# Reach_B0.net
KiCad netlist of a schematic drawn in EAGLE
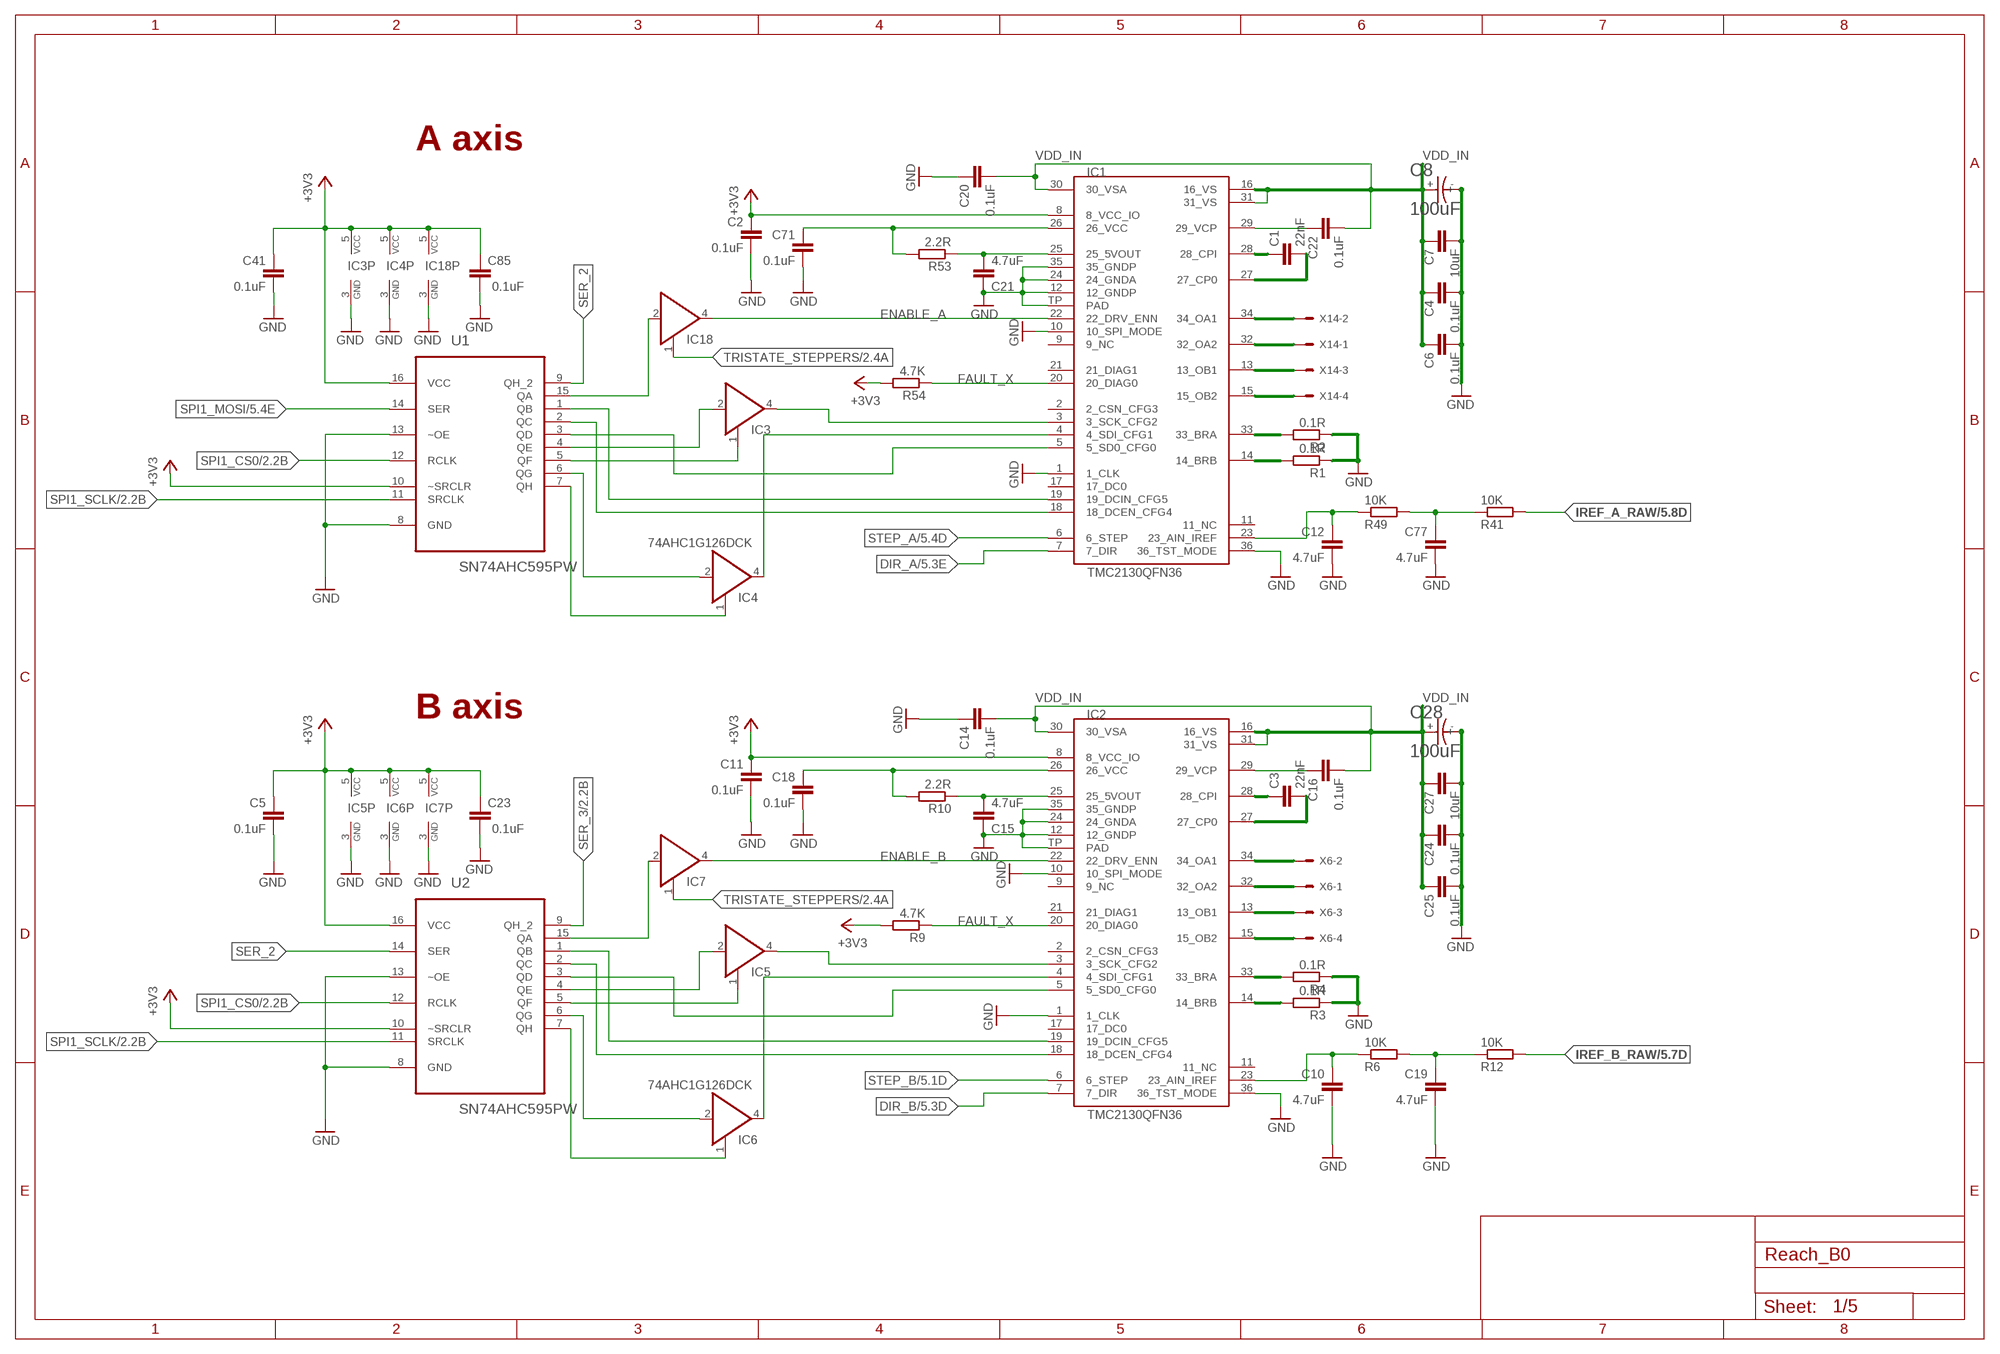
[diagram p0: schematic, sheet 1]
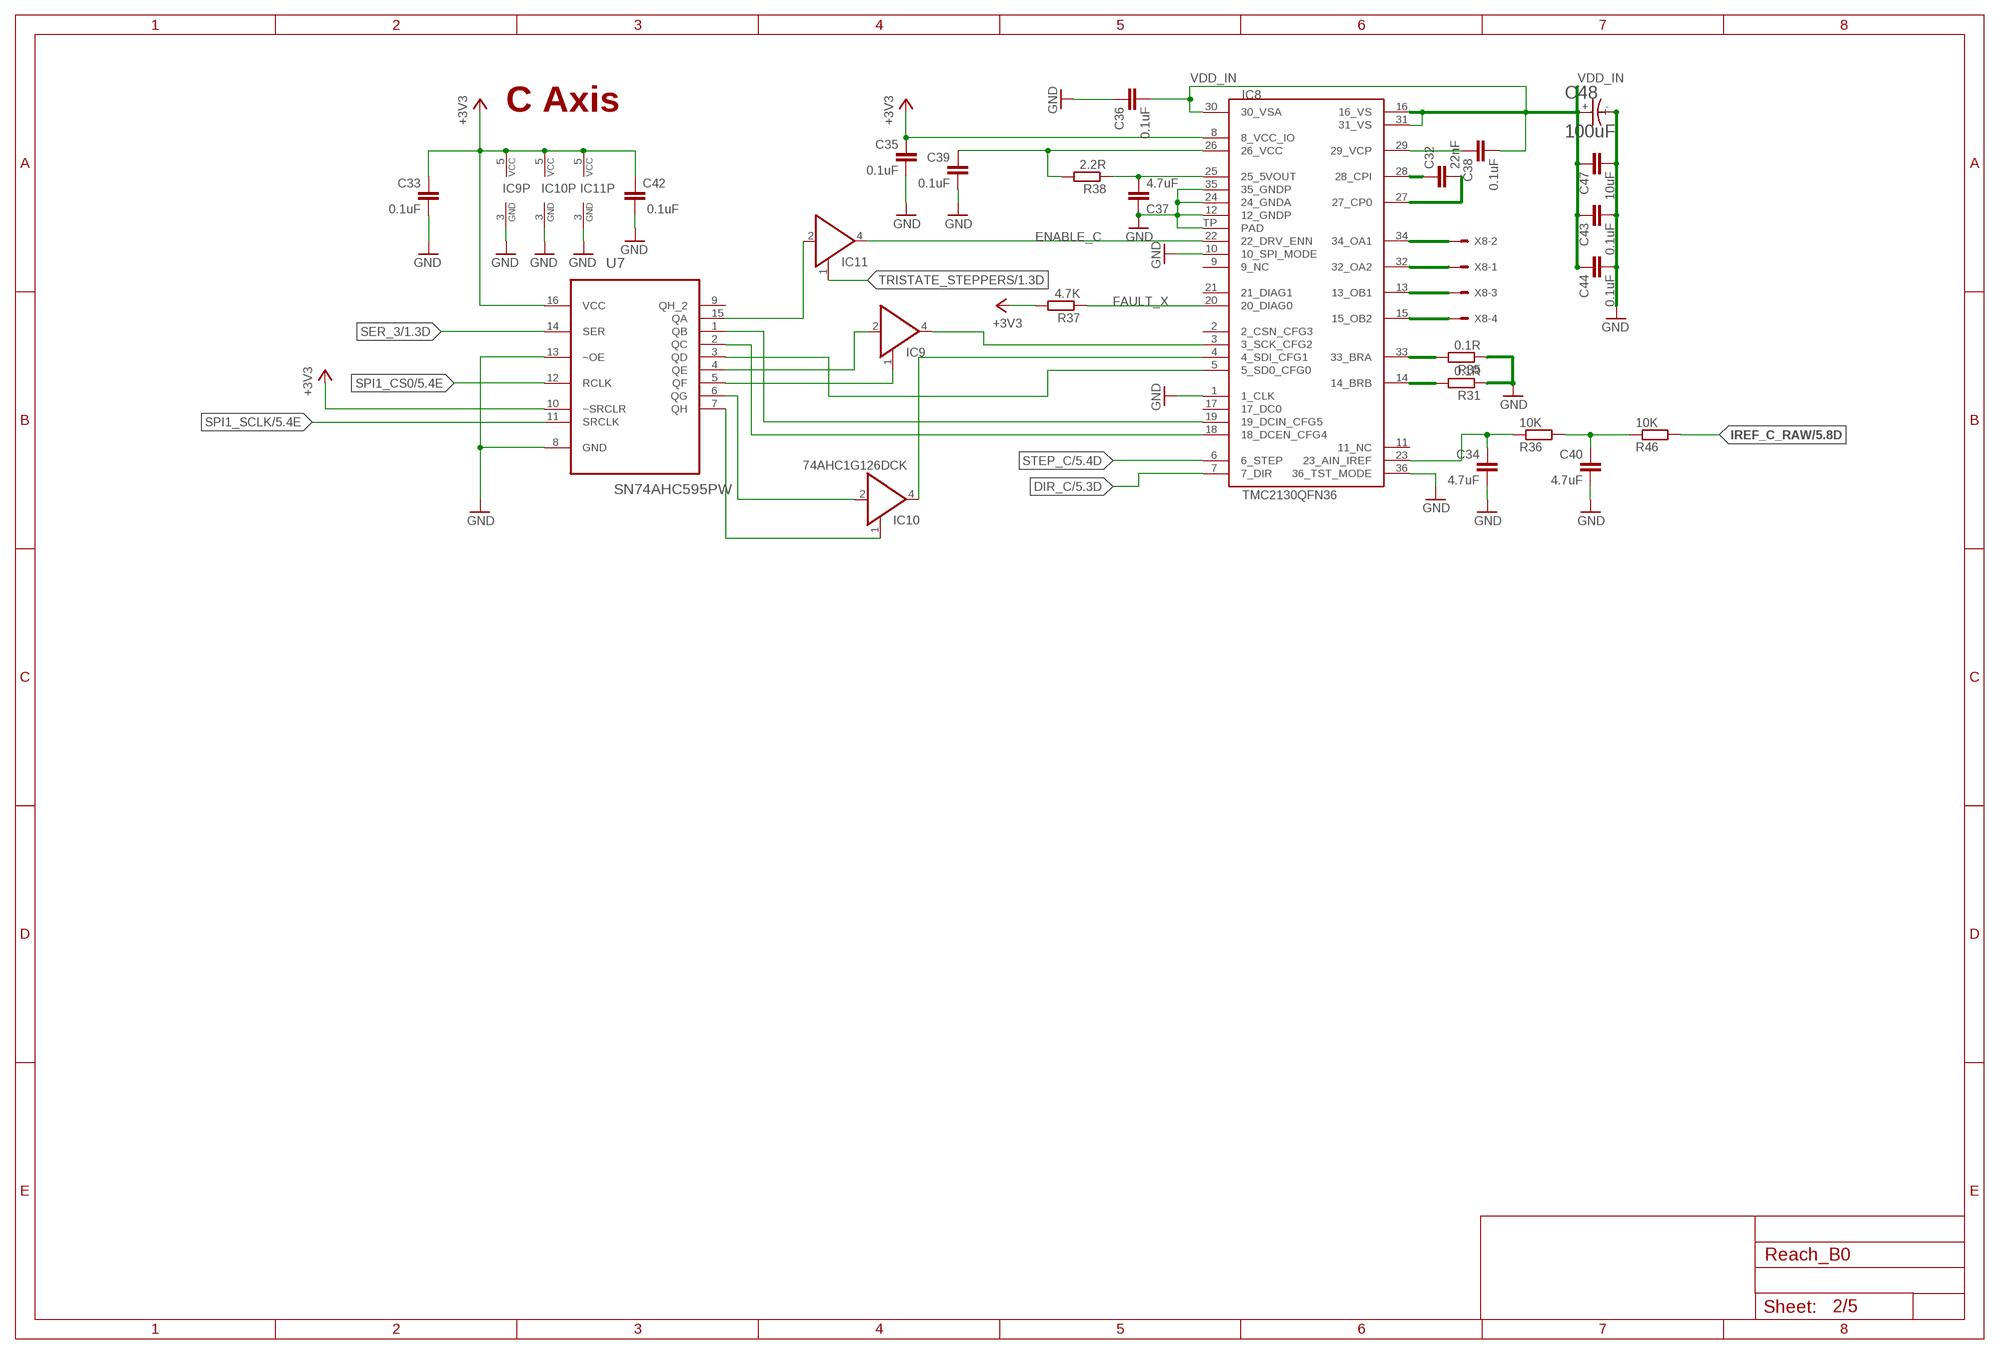
[diagram p1: schematic, sheet 2]
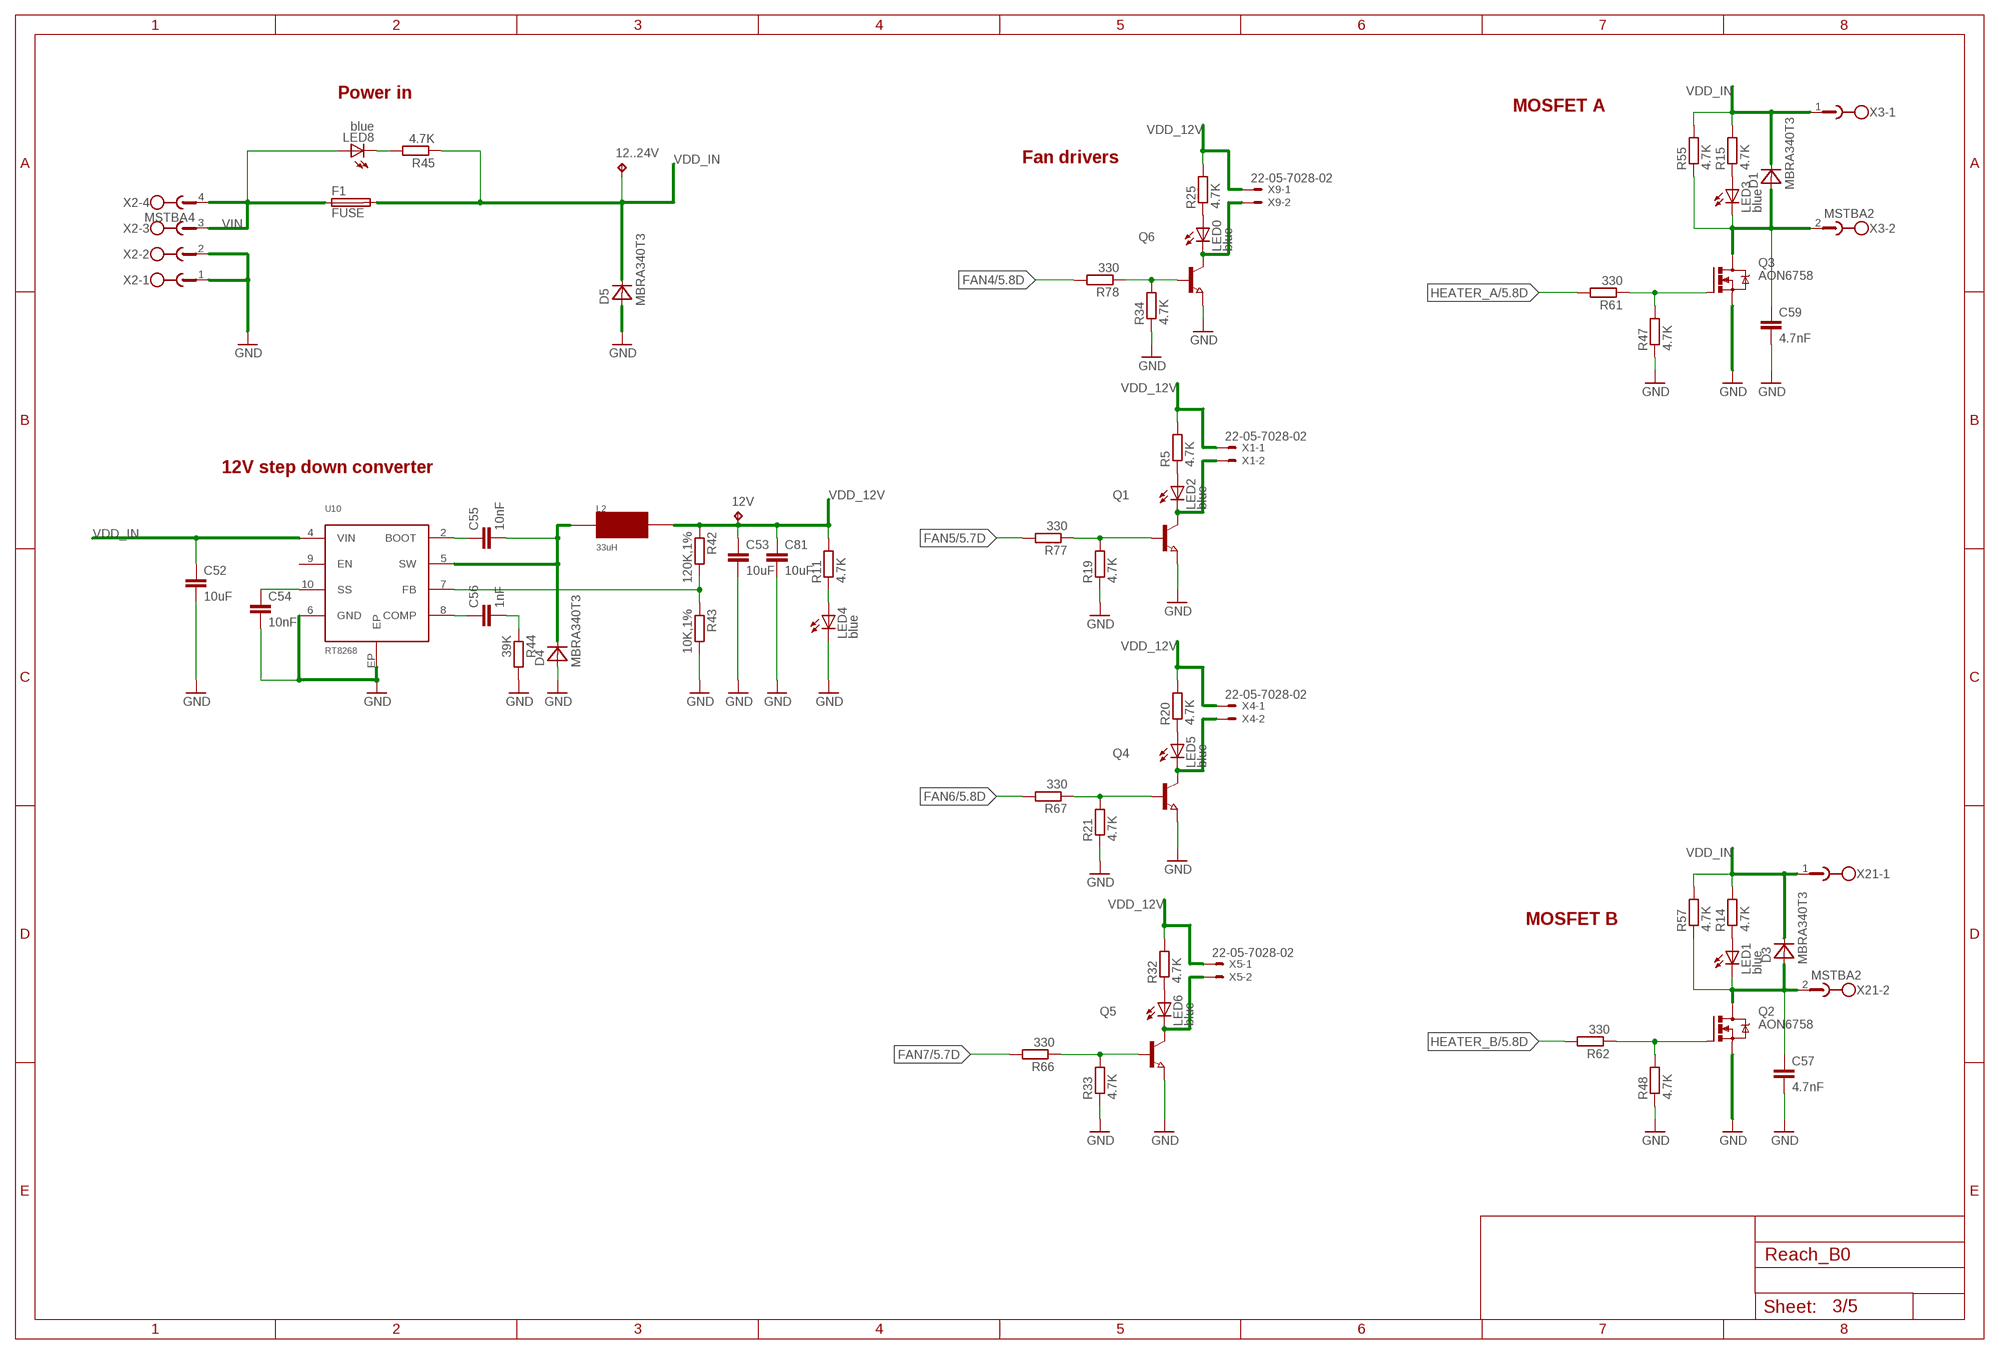
[diagram p2: schematic, sheet 3]
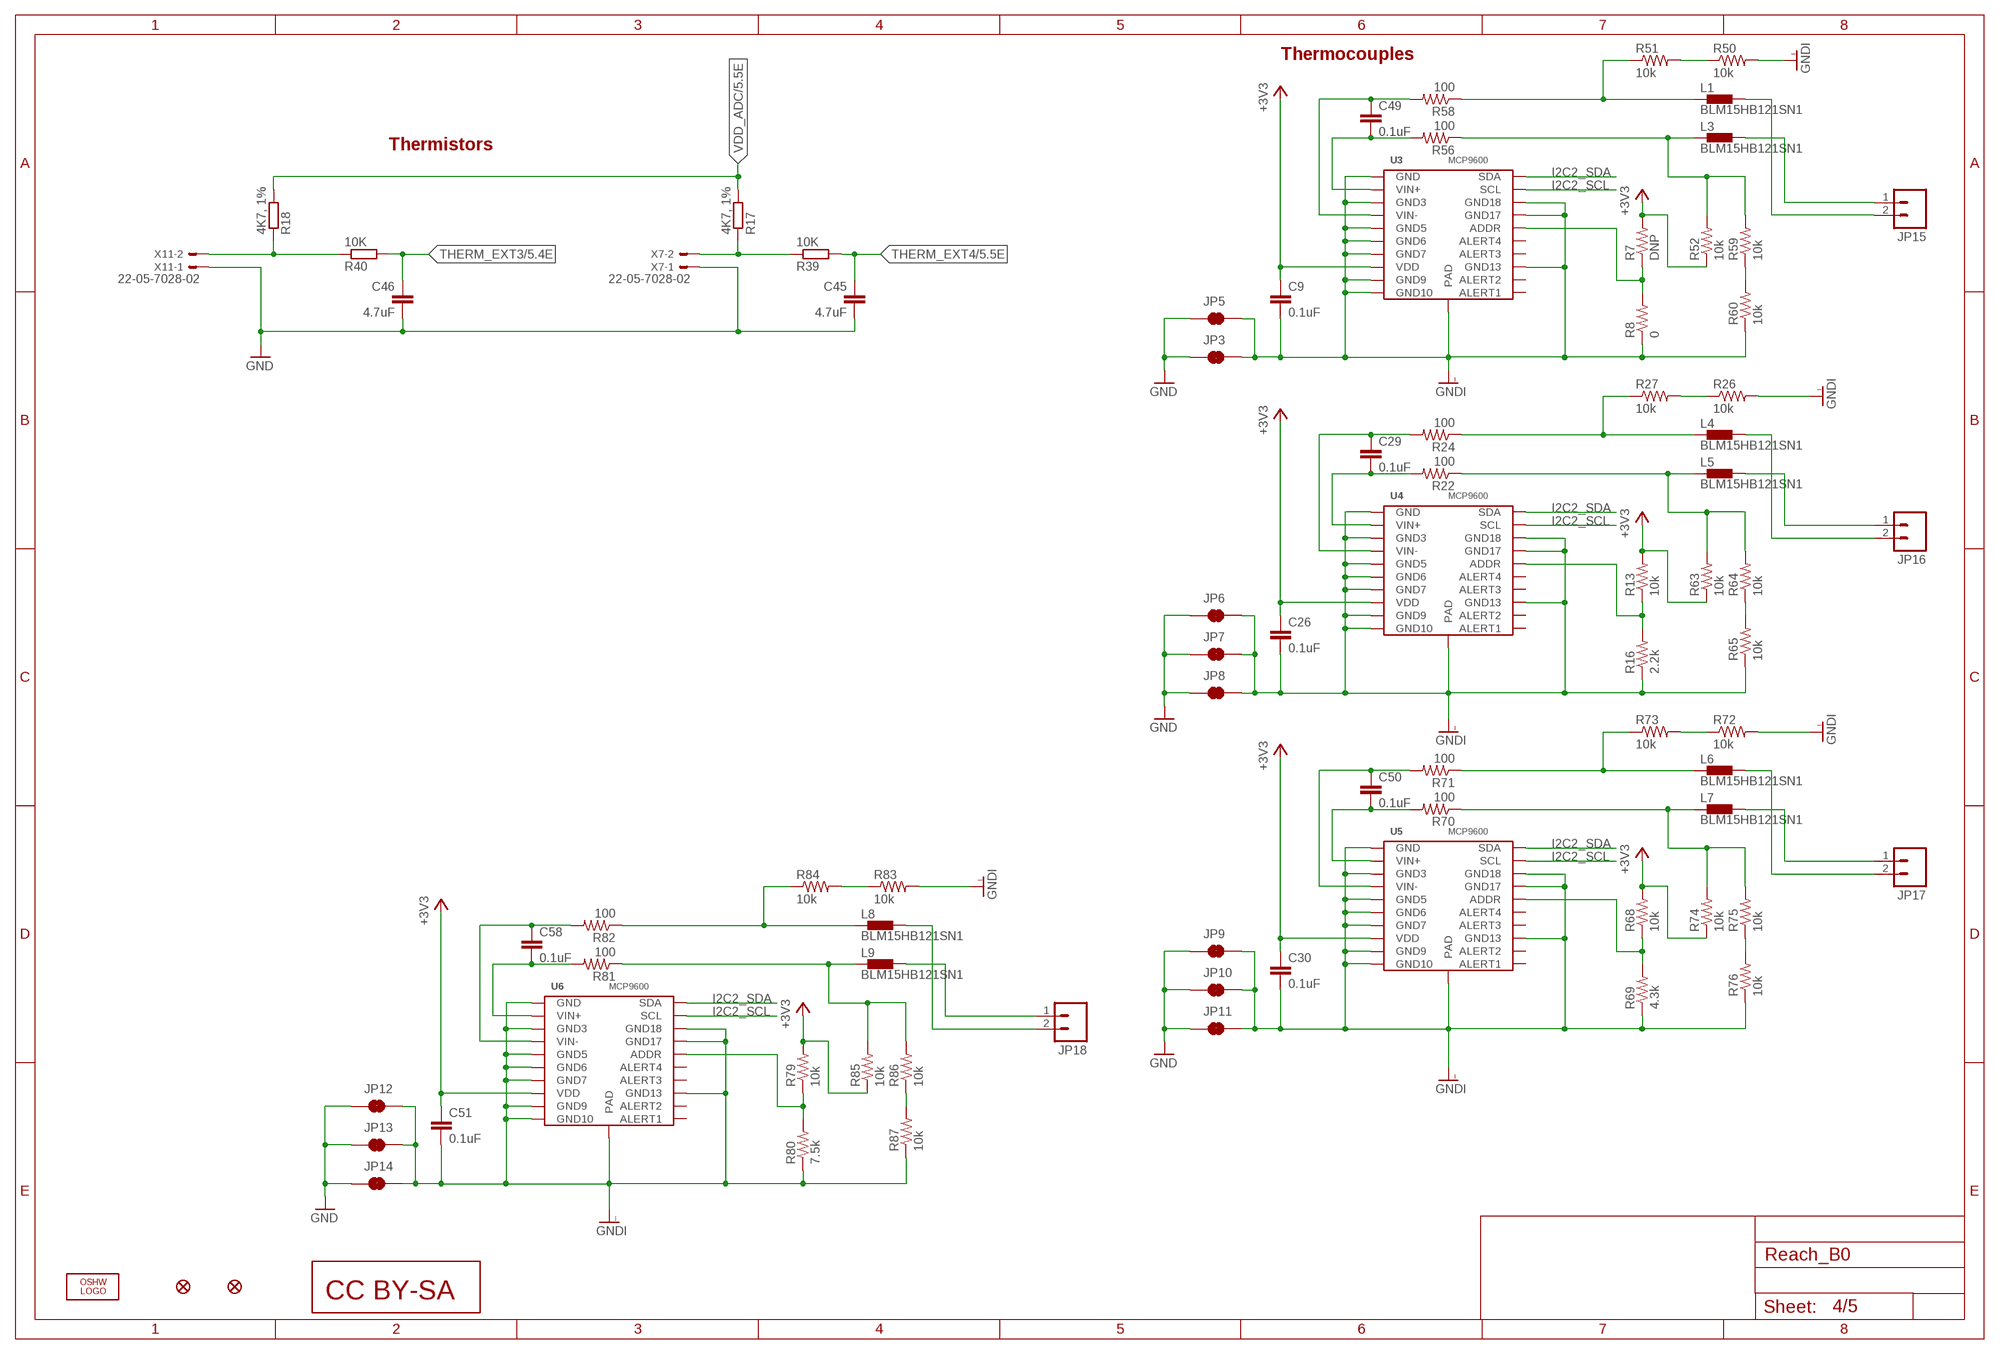
[diagram p3: schematic, sheet 4]
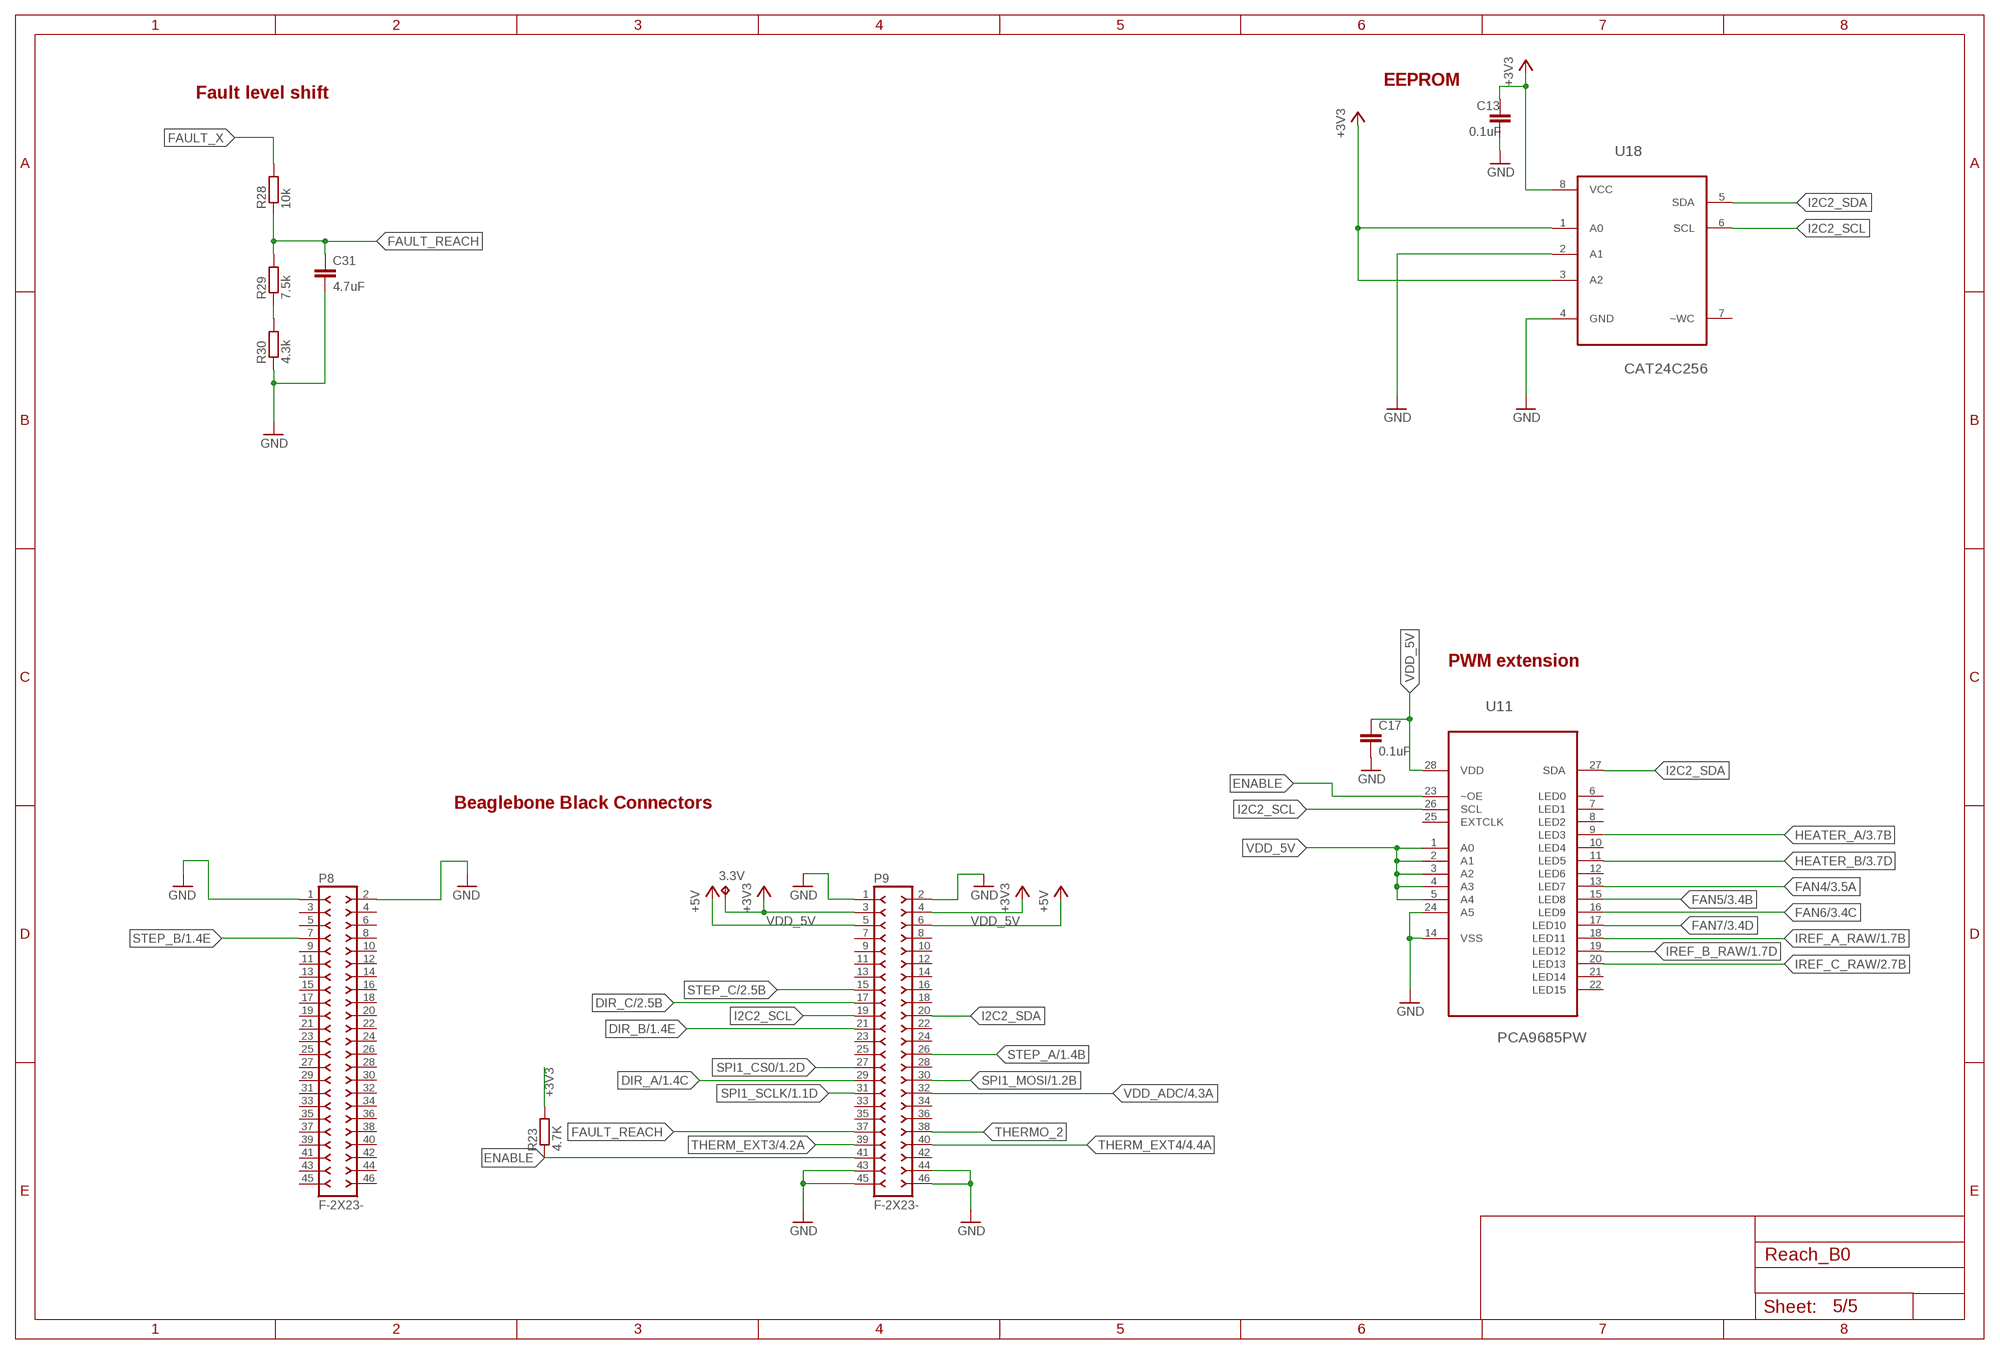
[diagram p4: schematic, sheet 5]

(export (version "E")
  (design (tool "Eeschema 10.0.6"))
  (components
    (comp (ref "C32")
      (value "22nF")
      (footprint "eagle-import:C0402")
      (libsource (lib "eagle-import") (part "C-EUC0402"))
    )
    (comp (ref "C33")
      (value "0.1uF")
      (footprint "eagle-import:C0402")
      (libsource (lib "eagle-import") (part "C-EUC0402"))
    )
    (comp (ref "C34")
      (value "4.7uF")
      (footprint "eagle-import:C0402")
      (libsource (lib "eagle-import") (part "C-EUC0402"))
    )
    (comp (ref "C35")
      (value "0.1uF")
      (footprint "eagle-import:C0402")
      (libsource (lib "eagle-import") (part "C-EUC0402"))
    )
    (comp (ref "C36")
      (value "0.1uF")
      (footprint "eagle-import:C0402")
      (libsource (lib "eagle-import") (part "C-EUC0402"))
    )
    (comp (ref "C37")
      (value "4.7uF")
      (footprint "eagle-import:C0402")
      (libsource (lib "eagle-import") (part "C-EUC0402"))
    )
    (comp (ref "C38")
      (value "0.1uF")
      (footprint "eagle-import:C0402")
      (libsource (lib "eagle-import") (part "C-EUC0402"))
    )
    (comp (ref "C39")
      (value "0.1uF")
      (footprint "eagle-import:C0402")
      (libsource (lib "eagle-import") (part "C-EUC0402"))
    )
    (comp (ref "C40")
      (value "4.7uF")
      (footprint "eagle-import:C0402")
      (libsource (lib "eagle-import") (part "C-EUC0402"))
    )
    (comp (ref "C42")
      (value "0.1uF")
      (footprint "eagle-import:C0402")
      (libsource (lib "eagle-import") (part "C-EUC0402"))
    )
    (comp (ref "C43")
      (value "0.1uF")
      (footprint "eagle-import:C0402")
      (fields (field (name "MPN") "CL10B104KB8NNND"))
      (libsource (lib "eagle-import") (part "C-EUC0402"))
    )
    (comp (ref "C44")
      (value "0.1uF")
      (footprint "eagle-import:C0402")
      (fields (field (name "MPN") "CL10B104KB8NNND"))
      (libsource (lib "eagle-import") (part "C-EUC0402"))
    )
    (comp (ref "C47")
      (value "10uF")
      (footprint "eagle-import:C0805")
      (fields (field (name "MPN") "C2012X5R1V106M085AC"))
      (libsource (lib "eagle-import") (part "C-EUC0805"))
    )
    (comp (ref "C48")
      (value "100uF")
      (footprint "eagle-import:RHS1V10MCN1GS")
      (fields (field (name "MPN") "RHS1V101MCN1GS"))
      (libsource (lib "eagle-import") (part "C"))
    )
    (comp (ref "IC8")
      (value "TMC2130QFN36")
      (footprint "eagle-import:QFN36")
      (libsource (lib "eagle-import") (part "TMC2130QFN36"))
    )
    (comp (ref "IC9")
      (value "74AHC1G126DCK")
      (footprint "eagle-import:SC70-5")
      (libsource (lib "eagle-import") (part "741G126DCKAHC"))
    )
    (comp (ref "IC10")
      (value "74AHC1G126DCK")
      (footprint "eagle-import:SC70-5")
      (libsource (lib "eagle-import") (part "741G126DCKAHC"))
    )
    (comp (ref "IC11")
      (value "74AHC1G126DCK")
      (footprint "eagle-import:SC70-5")
      (libsource (lib "eagle-import") (part "741G126DCKAHC"))
    )
    (comp (ref "R31")
      (value "0.1R")
      (footprint "eagle-import:R0805")
      (libsource (lib "eagle-import") (part "R-EU_R0805"))
    )
    (comp (ref "R35")
      (value "0.1R")
      (footprint "eagle-import:R0805")
      (libsource (lib "eagle-import") (part "R-EU_R0805"))
    )
    (comp (ref "R36")
      (value "10K")
      (footprint "eagle-import:R0402")
      (libsource (lib "eagle-import") (part "R-EU_R0402"))
    )
    (comp (ref "R37")
      (value "4.7K")
      (footprint "eagle-import:R0402")
      (libsource (lib "eagle-import") (part "R-EU_R0402"))
    )
    (comp (ref "R38")
      (value "2.2R")
      (footprint "eagle-import:R0402")
      (libsource (lib "eagle-import") (part "R-EU_R0402"))
    )
    (comp (ref "R46")
      (value "10K")
      (footprint "eagle-import:R0402")
      (libsource (lib "eagle-import") (part "R-EU_R0402"))
    )
    (comp (ref "U7")
      (value "SN74AHC595PW")
      (footprint "eagle-import:SOP65P640X120-16N")
      (libsource (lib "eagle-import") (part "SN74AHC595PW"))
    )
    (comp (ref "X8")
      (value "22-05-7048-04")
      (footprint "eagle-import:7395-04")
      (libsource (lib "eagle-import") (part "22-?-0405-7048"))
    )
    (comp (ref "C1")
      (value "22nF")
      (footprint "eagle-import:C0402")
      (libsource (lib "eagle-import") (part "C-EUC0402"))
    )
    (comp (ref "C2")
      (value "0.1uF")
      (footprint "eagle-import:C0402")
      (libsource (lib "eagle-import") (part "C-EUC0402"))
    )
    (comp (ref "C3")
      (value "22nF")
      (footprint "eagle-import:C0402")
      (libsource (lib "eagle-import") (part "C-EUC0402"))
    )
    (comp (ref "C4")
      (value "0.1uF")
      (footprint "eagle-import:C0402")
      (fields (field (name "MPN") "CL10B104KB8NNND"))
      (libsource (lib "eagle-import") (part "C-EUC0402"))
    )
    (comp (ref "C5")
      (value "0.1uF")
      (footprint "eagle-import:C0402")
      (libsource (lib "eagle-import") (part "C-EUC0402"))
    )
    (comp (ref "C6")
      (value "0.1uF")
      (footprint "eagle-import:C0402")
      (fields (field (name "MPN") "CL10B104KB8NNND"))
      (libsource (lib "eagle-import") (part "C-EUC0402"))
    )
    (comp (ref "C7")
      (value "10uF")
      (footprint "eagle-import:C0805")
      (fields (field (name "MPN") "C2012X5R1V106M085AC"))
      (libsource (lib "eagle-import") (part "C-EUC0805"))
    )
    (comp (ref "C8")
      (value "100uF")
      (footprint "eagle-import:RHS1V10MCN1GS")
      (fields (field (name "MPN") "RHS1V101MCN1GS"))
      (libsource (lib "eagle-import") (part "C"))
    )
    (comp (ref "C10")
      (value "4.7uF")
      (footprint "eagle-import:C0402")
      (libsource (lib "eagle-import") (part "C-EUC0402"))
    )
    (comp (ref "C11")
      (value "0.1uF")
      (footprint "eagle-import:C0402")
      (libsource (lib "eagle-import") (part "C-EUC0402"))
    )
    (comp (ref "C12")
      (value "4.7uF")
      (footprint "eagle-import:C0402")
      (libsource (lib "eagle-import") (part "C-EUC0402"))
    )
    (comp (ref "C14")
      (value "0.1uF")
      (footprint "eagle-import:C0402")
      (libsource (lib "eagle-import") (part "C-EUC0402"))
    )
    (comp (ref "C15")
      (value "4.7uF")
      (footprint "eagle-import:C0402")
      (libsource (lib "eagle-import") (part "C-EUC0402"))
    )
    (comp (ref "C16")
      (value "0.1uF")
      (footprint "eagle-import:C0402")
      (libsource (lib "eagle-import") (part "C-EUC0402"))
    )
    (comp (ref "C18")
      (value "0.1uF")
      (footprint "eagle-import:C0402")
      (libsource (lib "eagle-import") (part "C-EUC0402"))
    )
    (comp (ref "C19")
      (value "4.7uF")
      (footprint "eagle-import:C0402")
      (libsource (lib "eagle-import") (part "C-EUC0402"))
    )
    (comp (ref "C20")
      (value "0.1uF")
      (footprint "eagle-import:C0402")
      (libsource (lib "eagle-import") (part "C-EUC0402"))
    )
    (comp (ref "C21")
      (value "4.7uF")
      (footprint "eagle-import:C0402")
      (libsource (lib "eagle-import") (part "C-EUC0402"))
    )
    (comp (ref "C22")
      (value "0.1uF")
      (footprint "eagle-import:C0402")
      (libsource (lib "eagle-import") (part "C-EUC0402"))
    )
    (comp (ref "C23")
      (value "0.1uF")
      (footprint "eagle-import:C0402")
      (libsource (lib "eagle-import") (part "C-EUC0402"))
    )
    (comp (ref "C24")
      (value "0.1uF")
      (footprint "eagle-import:C0402")
      (fields (field (name "MPN") "CL10B104KB8NNND"))
      (libsource (lib "eagle-import") (part "C-EUC0402"))
    )
    (comp (ref "C25")
      (value "0.1uF")
      (footprint "eagle-import:C0402")
      (fields (field (name "MPN") "CL10B104KB8NNND"))
      (libsource (lib "eagle-import") (part "C-EUC0402"))
    )
    (comp (ref "C27")
      (value "10uF")
      (footprint "eagle-import:C0805")
      (fields (field (name "MPN") "C2012X5R1V106M085AC"))
      (libsource (lib "eagle-import") (part "C-EUC0805"))
    )
    (comp (ref "C28")
      (value "100uF")
      (footprint "eagle-import:RHS1V10MCN1GS")
      (fields (field (name "MPN") "RHS1V101MCN1GS"))
      (libsource (lib "eagle-import") (part "C"))
    )
    (comp (ref "C41")
      (value "0.1uF")
      (footprint "eagle-import:C0402")
      (libsource (lib "eagle-import") (part "C-EUC0402"))
    )
    (comp (ref "C71")
      (value "0.1uF")
      (footprint "eagle-import:C0402")
      (libsource (lib "eagle-import") (part "C-EUC0402"))
    )
    (comp (ref "C77")
      (value "4.7uF")
      (footprint "eagle-import:C0402")
      (libsource (lib "eagle-import") (part "C-EUC0402"))
    )
    (comp (ref "C85")
      (value "0.1uF")
      (footprint "eagle-import:C0402")
      (libsource (lib "eagle-import") (part "C-EUC0402"))
    )
    (comp (ref "IC1")
      (value "TMC2130QFN36")
      (footprint "eagle-import:QFN36")
      (libsource (lib "eagle-import") (part "TMC2130QFN36"))
    )
    (comp (ref "IC2")
      (value "TMC2130QFN36")
      (footprint "eagle-import:QFN36")
      (libsource (lib "eagle-import") (part "TMC2130QFN36"))
    )
    (comp (ref "IC3")
      (value "74AHC1G126DCK")
      (footprint "eagle-import:SC70-5")
      (libsource (lib "eagle-import") (part "741G126DCKAHC"))
    )
    (comp (ref "IC4")
      (value "74AHC1G126DCK")
      (footprint "eagle-import:SC70-5")
      (libsource (lib "eagle-import") (part "741G126DCKAHC"))
    )
    (comp (ref "IC5")
      (value "74AHC1G126DCK")
      (footprint "eagle-import:SC70-5")
      (libsource (lib "eagle-import") (part "741G126DCKAHC"))
    )
    (comp (ref "IC6")
      (value "74AHC1G126DCK")
      (footprint "eagle-import:SC70-5")
      (libsource (lib "eagle-import") (part "741G126DCKAHC"))
    )
    (comp (ref "IC7")
      (value "74AHC1G126DCK")
      (footprint "eagle-import:SC70-5")
      (libsource (lib "eagle-import") (part "741G126DCKAHC"))
    )
    (comp (ref "IC18")
      (value "74AHC1G126DCK")
      (footprint "eagle-import:SC70-5")
      (libsource (lib "eagle-import") (part "741G126DCKAHC"))
    )
    (comp (ref "R1")
      (value "0.1R")
      (footprint "eagle-import:R0805")
      (libsource (lib "eagle-import") (part "R-EU_R0805"))
    )
    (comp (ref "R2")
      (value "0.1R")
      (footprint "eagle-import:R0805")
      (libsource (lib "eagle-import") (part "R-EU_R0805"))
    )
    (comp (ref "R3")
      (value "0.1R")
      (footprint "eagle-import:R0805")
      (libsource (lib "eagle-import") (part "R-EU_R0805"))
    )
    (comp (ref "R4")
      (value "0.1R")
      (footprint "eagle-import:R0805")
      (libsource (lib "eagle-import") (part "R-EU_R0805"))
    )
    (comp (ref "R6")
      (value "10K")
      (footprint "eagle-import:R0402")
      (libsource (lib "eagle-import") (part "R-EU_R0402"))
    )
    (comp (ref "R9")
      (value "4.7K")
      (footprint "eagle-import:R0402")
      (libsource (lib "eagle-import") (part "R-EU_R0402"))
    )
    (comp (ref "R10")
      (value "2.2R")
      (footprint "eagle-import:R0402")
      (libsource (lib "eagle-import") (part "R-EU_R0402"))
    )
    (comp (ref "R12")
      (value "10K")
      (footprint "eagle-import:R0402")
      (libsource (lib "eagle-import") (part "R-EU_R0402"))
    )
    (comp (ref "R41")
      (value "10K")
      (footprint "eagle-import:R0402")
      (libsource (lib "eagle-import") (part "R-EU_R0402"))
    )
    (comp (ref "R49")
      (value "10K")
      (footprint "eagle-import:R0402")
      (libsource (lib "eagle-import") (part "R-EU_R0402"))
    )
    (comp (ref "R53")
      (value "2.2R")
      (footprint "eagle-import:R0402")
      (libsource (lib "eagle-import") (part "R-EU_R0402"))
    )
    (comp (ref "R54")
      (value "4.7K")
      (footprint "eagle-import:R0402")
      (libsource (lib "eagle-import") (part "R-EU_R0402"))
    )
    (comp (ref "U1")
      (value "SN74AHC595PW")
      (footprint "eagle-import:SOP65P640X120-16N")
      (libsource (lib "eagle-import") (part "SN74AHC595PW"))
    )
    (comp (ref "U2")
      (value "SN74AHC595PW")
      (footprint "eagle-import:SOP65P640X120-16N")
      (libsource (lib "eagle-import") (part "SN74AHC595PW"))
    )
    (comp (ref "X6")
      (value "22-05-7048-04")
      (footprint "eagle-import:7395-04")
      (libsource (lib "eagle-import") (part "22-?-0405-7048"))
    )
    (comp (ref "X14")
      (value "22-05-7048-04")
      (footprint "eagle-import:7395-04")
      (libsource (lib "eagle-import") (part "22-?-0405-7048"))
    )
    (comp (ref "3.3V")
      (value "TPB1,27")
      (footprint "eagle-import:B1,27")
      (libsource (lib "eagle-import") (part "TPB1,27"))
    )
    (comp (ref "C13")
      (value "0.1uF")
      (footprint "eagle-import:C0402")
      (libsource (lib "eagle-import") (part "C-EUC0402"))
    )
    (comp (ref "C17")
      (value "0.1uF")
      (footprint "eagle-import:C0402")
      (libsource (lib "eagle-import") (part "C-EUC0402"))
    )
    (comp (ref "C31")
      (value "4.7uF")
      (footprint "eagle-import:C0402")
      (libsource (lib "eagle-import") (part "C-EUC0402"))
    )
    (comp (ref "P8")
      (value "F-2X23-")
      (footprint "eagle-import:DIL-100-2X23")
      (libsource (lib "eagle-import") (part "F-2X23-"))
    )
    (comp (ref "P9")
      (value "F-2X23-")
      (footprint "eagle-import:DIL-100-2X23")
      (libsource (lib "eagle-import") (part "F-2X23-"))
    )
    (comp (ref "R23")
      (value "4.7K")
      (footprint "eagle-import:R0402")
      (libsource (lib "eagle-import") (part "R-EU_R0402"))
    )
    (comp (ref "R28")
      (value "10k")
      (footprint "eagle-import:R0402")
      (libsource (lib "eagle-import") (part "R-EU_R0402"))
    )
    (comp (ref "R29")
      (value "7.5k")
      (footprint "eagle-import:R0402")
      (libsource (lib "eagle-import") (part "R-EU_R0402"))
    )
    (comp (ref "R30")
      (value "4.3k")
      (footprint "eagle-import:R0402")
      (libsource (lib "eagle-import") (part "R-EU_R0402"))
    )
    (comp (ref "U11")
      (value "PCA9685PW")
      (footprint "eagle-import:SOP65P640X110-28N")
      (libsource (lib "eagle-import") (part "PCA9685PW"))
    )
    (comp (ref "U18")
      (value "CAT24C256")
      (footprint "eagle-import:SOIC127P600X175-8N")
      (libsource (lib "eagle-import") (part "CAT24C256"))
    )
    (comp (ref "12..24V")
      (value "TPB1,27")
      (footprint "eagle-import:B1,27")
      (libsource (lib "eagle-import") (part "TPB1,27"))
    )
    (comp (ref "12V")
      (value "TPB1,27")
      (footprint "eagle-import:B1,27")
      (libsource (lib "eagle-import") (part "TPB1,27"))
    )
    (comp (ref "C52")
      (value "10uF")
      (footprint "eagle-import:C1206")
      (fields (field (name "MPN") "CL31B106KAHNNNE"))
      (libsource (lib "eagle-import") (part "C-EUC1206"))
    )
    (comp (ref "C53")
      (value "10uF")
      (footprint "eagle-import:C1206")
      (fields (field (name "MPN") "CL31B106KAHNNNE"))
      (libsource (lib "eagle-import") (part "C-EUC1206"))
    )
    (comp (ref "C54")
      (value "10nF")
      (footprint "eagle-import:C0402")
      (fields (field (name "MPN") "CL05B103KB5NNNC"))
      (libsource (lib "eagle-import") (part "C-EUC0402"))
    )
    (comp (ref "C55")
      (value "10nF")
      (footprint "eagle-import:C0402")
      (fields (field (name "MPN") "CL05B103KB5NNNC"))
      (libsource (lib "eagle-import") (part "C-EUC0402"))
    )
    (comp (ref "C56")
      (value "1nF")
      (footprint "eagle-import:C0402")
      (fields (field (name "MPN") "C1005X7R1H102K050BA"))
      (libsource (lib "eagle-import") (part "C-EUC0402"))
    )
    (comp (ref "C57")
      (value "4.7nF")
      (footprint "eagle-import:C0402")
      (libsource (lib "eagle-import") (part "C-EUC0402"))
    )
    (comp (ref "C59")
      (value "4.7nF")
      (footprint "eagle-import:C0402")
      (libsource (lib "eagle-import") (part "C-EUC0402"))
    )
    (comp (ref "C81")
      (value "10uF")
      (footprint "eagle-import:C1206")
      (fields (field (name "MPN") "CL31B106KAHNNNE"))
      (libsource (lib "eagle-import") (part "C-EUC1206"))
    )
    (comp (ref "D1")
      (value "MBRA340T3")
      (footprint "eagle-import:SMA")
      (libsource (lib "eagle-import") (part "MBRA340T3"))
    )
    (comp (ref "D3")
      (value "MBRA340T3")
      (footprint "eagle-import:SMA")
      (libsource (lib "eagle-import") (part "MBRA340T3"))
    )
    (comp (ref "D4")
      (value "MBRA340T3")
      (footprint "eagle-import:SMA")
      (fields (field (name "MPN") "MBRA340T3G"))
      (libsource (lib "eagle-import") (part "MBRA340T3"))
    )
    (comp (ref "D5")
      (value "MBRA340T3")
      (footprint "eagle-import:SMA")
      (libsource (lib "eagle-import") (part "MBRA340T3"))
    )
    (comp (ref "F1")
      (value "FUSE")
      (footprint "eagle-import:3557")
      (libsource (lib "eagle-import") (part "FUSE"))
    )
    (comp (ref "L2")
      (value "33uH")
      (footprint "eagle-import:NR8040T330")
      (fields (field (name "MPN") "NR8040T330M"))
      (libsource (lib "eagle-import") (part "RT8040T330"))
    )
    (comp (ref "LED0")
      (value "blue")
      (footprint "eagle-import:CHIP-LED0603")
      (fields (field (name "MPN") "Q65110A7211"))
      (libsource (lib "eagle-import") (part "LEDCHIP-LED0603"))
    )
    (comp (ref "LED1")
      (value "blue")
      (footprint "eagle-import:CHIP-LED0603")
      (libsource (lib "eagle-import") (part "LEDCHIP-LED0603"))
    )
    (comp (ref "LED2")
      (value "blue")
      (footprint "eagle-import:CHIP-LED0603")
      (fields (field (name "MPN") "Q65110A7211"))
      (libsource (lib "eagle-import") (part "LEDCHIP-LED0603"))
    )
    (comp (ref "LED3")
      (value "blue")
      (footprint "eagle-import:CHIP-LED0603")
      (libsource (lib "eagle-import") (part "LEDCHIP-LED0603"))
    )
    (comp (ref "LED4")
      (value "blue")
      (footprint "eagle-import:CHIP-LED0603")
      (fields (field (name "MPN") "Q65110A7211"))
      (libsource (lib "eagle-import") (part "LEDCHIP-LED0603"))
    )
    (comp (ref "LED5")
      (value "blue")
      (footprint "eagle-import:CHIP-LED0603")
      (fields (field (name "MPN") "Q65110A7211"))
      (libsource (lib "eagle-import") (part "LEDCHIP-LED0603"))
    )
    (comp (ref "LED6")
      (value "blue")
      (footprint "eagle-import:CHIP-LED0603")
      (fields (field (name "MPN") "Q65110A7211"))
      (libsource (lib "eagle-import") (part "LEDCHIP-LED0603"))
    )
    (comp (ref "LED8")
      (value "blue")
      (footprint "eagle-import:CHIP-LED0603")
      (libsource (lib "eagle-import") (part "LEDCHIP-LED0603"))
    )
    (comp (ref "Q1")
      (value "NPN-TRANSISTOR_SOT23")
      (footprint "eagle-import:SOT23")
      (fields (field (name "MPN") "AO7400"))
      (libsource (lib "eagle-import") (part "NPN-TRANSISTOR_SOT23"))
    )
    (comp (ref "Q2")
      (value "AON6758")
      (footprint "eagle-import:8-DFN-EP-(5X6)")
      (libsource (lib "eagle-import") (part "AON6758"))
    )
    (comp (ref "Q3")
      (value "AON6758")
      (footprint "eagle-import:8-DFN-EP-(5X6)")
      (libsource (lib "eagle-import") (part "AON6758"))
    )
    (comp (ref "Q4")
      (value "NPN-TRANSISTOR_SOT23")
      (footprint "eagle-import:SOT23")
      (fields (field (name "MPN") "AO7400"))
      (libsource (lib "eagle-import") (part "NPN-TRANSISTOR_SOT23"))
    )
    (comp (ref "Q5")
      (value "NPN-TRANSISTOR_SOT23")
      (footprint "eagle-import:SOT23")
      (fields (field (name "MPN") "AO7400"))
      (libsource (lib "eagle-import") (part "NPN-TRANSISTOR_SOT23"))
    )
    (comp (ref "Q6")
      (value "NPN-TRANSISTOR_SOT23")
      (footprint "eagle-import:SOT23")
      (fields (field (name "MPN") "AO7400"))
      (libsource (lib "eagle-import") (part "NPN-TRANSISTOR_SOT23"))
    )
    (comp (ref "R5")
      (value "4.7K")
      (footprint "eagle-import:R0402")
      (fields (field (name "MPN") "RC0402JR-074K7L"))
      (libsource (lib "eagle-import") (part "R-EU_R0402"))
    )
    (comp (ref "R11")
      (value "4.7K")
      (footprint "eagle-import:R0402")
      (fields (field (name "MPN") "RC0402JR-074K7L"))
      (libsource (lib "eagle-import") (part "R-EU_R0402"))
    )
    (comp (ref "R14")
      (value "4.7K")
      (footprint "eagle-import:R0402")
      (libsource (lib "eagle-import") (part "R-EU_R0402"))
    )
    (comp (ref "R15")
      (value "4.7K")
      (footprint "eagle-import:R0402")
      (libsource (lib "eagle-import") (part "R-EU_R0402"))
    )
    (comp (ref "R19")
      (value "4.7K")
      (footprint "eagle-import:R0402")
      (fields (field (name "MPN") "RC0402JR-074K7L"))
      (libsource (lib "eagle-import") (part "R-EU_R0402"))
    )
    (comp (ref "R20")
      (value "4.7K")
      (footprint "eagle-import:R0402")
      (fields (field (name "MPN") "RC0402JR-074K7L"))
      (libsource (lib "eagle-import") (part "R-EU_R0402"))
    )
    (comp (ref "R21")
      (value "4.7K")
      (footprint "eagle-import:R0402")
      (fields (field (name "MPN") "RC0402JR-074K7L"))
      (libsource (lib "eagle-import") (part "R-EU_R0402"))
    )
    (comp (ref "R25")
      (value "4.7K")
      (footprint "eagle-import:R0402")
      (fields (field (name "MPN") "RC0402JR-074K7L"))
      (libsource (lib "eagle-import") (part "R-EU_R0402"))
    )
    (comp (ref "R32")
      (value "4.7K")
      (footprint "eagle-import:R0402")
      (fields (field (name "MPN") "RC0402JR-074K7L"))
      (libsource (lib "eagle-import") (part "R-EU_R0402"))
    )
    (comp (ref "R33")
      (value "4.7K")
      (footprint "eagle-import:R0402")
      (fields (field (name "MPN") "RC0402JR-074K7L"))
      (libsource (lib "eagle-import") (part "R-EU_R0402"))
    )
    (comp (ref "R34")
      (value "4.7K")
      (footprint "eagle-import:R0402")
      (fields (field (name "MPN") "RC0402JR-074K7L"))
      (libsource (lib "eagle-import") (part "R-EU_R0402"))
    )
    (comp (ref "R42")
      (value "120K,1%")
      (footprint "eagle-import:R0402")
      (fields (field (name "MPN") "RMCF0402FT120K"))
      (libsource (lib "eagle-import") (part "R-EU_R0402"))
    )
    (comp (ref "R43")
      (value "10K,1%")
      (footprint "eagle-import:R0402")
      (fields (field (name "MPN") "RC0402FR-0710KL"))
      (libsource (lib "eagle-import") (part "R-EU_R0402"))
    )
    (comp (ref "R44")
      (value "39K")
      (footprint "eagle-import:R0402")
      (fields (field (name "MPN") "RC1005J393CS"))
      (libsource (lib "eagle-import") (part "R-EU_R0402"))
    )
    (comp (ref "R45")
      (value "4.7K")
      (footprint "eagle-import:R0402")
      (libsource (lib "eagle-import") (part "R-EU_R0402"))
    )
    (comp (ref "R47")
      (value "4.7K")
      (footprint "eagle-import:R0402")
      (libsource (lib "eagle-import") (part "R-EU_R0402"))
    )
    (comp (ref "R48")
      (value "4.7K")
      (footprint "eagle-import:R0402")
      (libsource (lib "eagle-import") (part "R-EU_R0402"))
    )
    (comp (ref "R55")
      (value "4.7K")
      (footprint "eagle-import:R0402")
      (libsource (lib "eagle-import") (part "R-EU_R0402"))
    )
    (comp (ref "R57")
      (value "4.7K")
      (footprint "eagle-import:R0402")
      (libsource (lib "eagle-import") (part "R-EU_R0402"))
    )
    (comp (ref "R61")
      (value "330")
      (footprint "eagle-import:R0402")
      (libsource (lib "eagle-import") (part "R-EU_R0402"))
    )
    (comp (ref "R62")
      (value "330")
      (footprint "eagle-import:R0402")
      (libsource (lib "eagle-import") (part "R-EU_R0402"))
    )
    (comp (ref "R66")
      (value "330")
      (footprint "eagle-import:R0402")
      (libsource (lib "eagle-import") (part "R-EU_R0402"))
    )
    (comp (ref "R67")
      (value "330")
      (footprint "eagle-import:R0402")
      (libsource (lib "eagle-import") (part "R-EU_R0402"))
    )
    (comp (ref "R77")
      (value "330")
      (footprint "eagle-import:R0402")
      (libsource (lib "eagle-import") (part "R-EU_R0402"))
    )
    (comp (ref "R78")
      (value "330")
      (footprint "eagle-import:R0402")
      (libsource (lib "eagle-import") (part "R-EU_R0402"))
    )
    (comp (ref "U10")
      (value "RT8268")
      (footprint "eagle-import:MSOP10")
      (fields (field (name "MPN") "RT8268GFP"))
      (libsource (lib "eagle-import") (part "RT8268"))
    )
    (comp (ref "X1")
      (value "22-05-7028-02")
      (footprint "eagle-import:7395-02")
      (fields (field (name "MPN") "640455-2"))
      (libsource (lib "eagle-import") (part "22-?-0205-7028"))
    )
    (comp (ref "X2")
      (value "MSTBA4")
      (footprint "eagle-import:MSTBA4")
      (fields (field (name "MF") "FARNELL") (field (name "MPN") "1757268"))
      (libsource (lib "eagle-import") (part "MSTBA4"))
    )
    (comp (ref "X3")
      (value "MSTBA2")
      (footprint "eagle-import:MSTBA2")
      (fields (field (name "MF") "FARNELL") (field (name "MPN") "1757242"))
      (libsource (lib "eagle-import") (part "MSTBA2"))
    )
    (comp (ref "X4")
      (value "22-05-7028-02")
      (footprint "eagle-import:7395-02")
      (fields (field (name "MPN") "640455-2"))
      (libsource (lib "eagle-import") (part "22-?-0205-7028"))
    )
    (comp (ref "X5")
      (value "22-05-7028-02")
      (footprint "eagle-import:7395-02")
      (fields (field (name "MPN") "640455-2"))
      (libsource (lib "eagle-import") (part "22-?-0205-7028"))
    )
    (comp (ref "X9")
      (value "22-05-7028-02")
      (footprint "eagle-import:7395-02")
      (fields (field (name "MPN") "640455-2"))
      (libsource (lib "eagle-import") (part "22-?-0205-7028"))
    )
    (comp (ref "X21")
      (value "MSTBA2")
      (footprint "eagle-import:MSTBA2")
      (fields (field (name "MF") "FARNELL") (field (name "MPN") "1757242"))
      (libsource (lib "eagle-import") (part "MSTBA2"))
    )
    (comp (ref "C9")
      (value "0.1uF")
      (footprint "eagle-import:C0402")
      (libsource (lib "eagle-import") (part "C-EUC0402"))
    )
    (comp (ref "C26")
      (value "0.1uF")
      (footprint "eagle-import:C0402")
      (libsource (lib "eagle-import") (part "C-EUC0402"))
    )
    (comp (ref "C29")
      (value "0.1uF")
      (footprint "eagle-import:C0402")
      (libsource (lib "eagle-import") (part "C-EUC0402"))
    )
    (comp (ref "C30")
      (value "0.1uF")
      (footprint "eagle-import:C0402")
      (libsource (lib "eagle-import") (part "C-EUC0402"))
    )
    (comp (ref "C45")
      (value "4.7uF")
      (footprint "eagle-import:C0402")
      (fields (field (name "MPN") "GRM155R60J475ME47D"))
      (libsource (lib "eagle-import") (part "C-EUC0402"))
    )
    (comp (ref "C46")
      (value "4.7uF")
      (footprint "eagle-import:C0402")
      (fields (field (name "MPN") "GRM155R60J475ME47D"))
      (libsource (lib "eagle-import") (part "C-EUC0402"))
    )
    (comp (ref "C49")
      (value "0.1uF")
      (footprint "eagle-import:C0402")
      (libsource (lib "eagle-import") (part "C-EUC0402"))
    )
    (comp (ref "C50")
      (value "0.1uF")
      (footprint "eagle-import:C0402")
      (libsource (lib "eagle-import") (part "C-EUC0402"))
    )
    (comp (ref "C51")
      (value "0.1uF")
      (footprint "eagle-import:C0402")
      (libsource (lib "eagle-import") (part "C-EUC0402"))
    )
    (comp (ref "C58")
      (value "0.1uF")
      (footprint "eagle-import:C0402")
      (libsource (lib "eagle-import") (part "C-EUC0402"))
    )
    (comp (ref "JP1")
      (value "FIDUCIAL1X2.5")
      (footprint "eagle-import:FIDUCIAL-1X2.5")
      (libsource (lib "eagle-import") (part "FIDUCIAL1X2.5"))
    )
    (comp (ref "JP2")
      (value "FIDUCIAL1X2.5")
      (footprint "eagle-import:FIDUCIAL-1X2.5")
      (libsource (lib "eagle-import") (part "FIDUCIAL1X2.5"))
    )
    (comp (ref "JP3")
      (value "JUMPER-PAD-2-NC_BY_TRACE")
      (footprint "eagle-import:PAD-JUMPER-2-NC_BY_TRACE_YES_SILK")
      (libsource (lib "eagle-import") (part "JUMPER-PAD-2-NC_BY_TRACE"))
    )
    (comp (ref "JP5")
      (value "JUMPER-PAD-2-NC_BY_TRACE")
      (footprint "eagle-import:PAD-JUMPER-2-NC_BY_TRACE_YES_SILK")
      (libsource (lib "eagle-import") (part "JUMPER-PAD-2-NC_BY_TRACE"))
    )
    (comp (ref "JP6")
      (value "JUMPER-PAD-2-NC_BY_TRACE")
      (footprint "eagle-import:PAD-JUMPER-2-NC_BY_TRACE_YES_SILK")
      (libsource (lib "eagle-import") (part "JUMPER-PAD-2-NC_BY_TRACE"))
    )
    (comp (ref "JP7")
      (value "JUMPER-PAD-2-NC_BY_TRACE")
      (footprint "eagle-import:PAD-JUMPER-2-NC_BY_TRACE_YES_SILK")
      (libsource (lib "eagle-import") (part "JUMPER-PAD-2-NC_BY_TRACE"))
    )
    (comp (ref "JP8")
      (value "JUMPER-PAD-2-NC_BY_TRACE")
      (footprint "eagle-import:PAD-JUMPER-2-NC_BY_TRACE_YES_SILK")
      (libsource (lib "eagle-import") (part "JUMPER-PAD-2-NC_BY_TRACE"))
    )
    (comp (ref "JP9")
      (value "JUMPER-PAD-2-NC_BY_TRACE")
      (footprint "eagle-import:PAD-JUMPER-2-NC_BY_TRACE_YES_SILK")
      (libsource (lib "eagle-import") (part "JUMPER-PAD-2-NC_BY_TRACE"))
    )
    (comp (ref "JP10")
      (value "JUMPER-PAD-2-NC_BY_TRACE")
      (footprint "eagle-import:PAD-JUMPER-2-NC_BY_TRACE_YES_SILK")
      (libsource (lib "eagle-import") (part "JUMPER-PAD-2-NC_BY_TRACE"))
    )
    (comp (ref "JP11")
      (value "JUMPER-PAD-2-NC_BY_TRACE")
      (footprint "eagle-import:PAD-JUMPER-2-NC_BY_TRACE_YES_SILK")
      (libsource (lib "eagle-import") (part "JUMPER-PAD-2-NC_BY_TRACE"))
    )
    (comp (ref "JP12")
      (value "JUMPER-PAD-2-NC_BY_TRACE")
      (footprint "eagle-import:PAD-JUMPER-2-NC_BY_TRACE_YES_SILK")
      (libsource (lib "eagle-import") (part "JUMPER-PAD-2-NC_BY_TRACE"))
    )
    (comp (ref "JP13")
      (value "JUMPER-PAD-2-NC_BY_TRACE")
      (footprint "eagle-import:PAD-JUMPER-2-NC_BY_TRACE_YES_SILK")
      (libsource (lib "eagle-import") (part "JUMPER-PAD-2-NC_BY_TRACE"))
    )
    (comp (ref "JP14")
      (value "JUMPER-PAD-2-NC_BY_TRACE")
      (footprint "eagle-import:PAD-JUMPER-2-NC_BY_TRACE_YES_SILK")
      (libsource (lib "eagle-import") (part "JUMPER-PAD-2-NC_BY_TRACE"))
    )
    (comp (ref "JP15")
      (value "M025MM")
      (footprint "eagle-import:SCREWTERMINAL-5MM-2")
      (libsource (lib "eagle-import") (part "M025MM"))
    )
    (comp (ref "JP16")
      (value "M025MM")
      (footprint "eagle-import:SCREWTERMINAL-5MM-2")
      (libsource (lib "eagle-import") (part "M025MM"))
    )
    (comp (ref "JP17")
      (value "M025MM")
      (footprint "eagle-import:SCREWTERMINAL-5MM-2")
      (libsource (lib "eagle-import") (part "M025MM"))
    )
    (comp (ref "JP18")
      (value "M025MM")
      (footprint "eagle-import:SCREWTERMINAL-5MM-2")
      (libsource (lib "eagle-import") (part "M025MM"))
    )
    (comp (ref "L1")
      (value "BLM15HB121SN1")
      (footprint "eagle-import:0402")
      (libsource (lib "eagle-import") (part "BLM15HB121SN1"))
    )
    (comp (ref "L3")
      (value "BLM15HB121SN1")
      (footprint "eagle-import:0402")
      (libsource (lib "eagle-import") (part "BLM15HB121SN1"))
    )
    (comp (ref "L4")
      (value "BLM15HB121SN1")
      (footprint "eagle-import:0402")
      (libsource (lib "eagle-import") (part "BLM15HB121SN1"))
    )
    (comp (ref "L5")
      (value "BLM15HB121SN1")
      (footprint "eagle-import:0402")
      (libsource (lib "eagle-import") (part "BLM15HB121SN1"))
    )
    (comp (ref "L6")
      (value "BLM15HB121SN1")
      (footprint "eagle-import:0402")
      (libsource (lib "eagle-import") (part "BLM15HB121SN1"))
    )
    (comp (ref "L7")
      (value "BLM15HB121SN1")
      (footprint "eagle-import:0402")
      (libsource (lib "eagle-import") (part "BLM15HB121SN1"))
    )
    (comp (ref "L8")
      (value "BLM15HB121SN1")
      (footprint "eagle-import:0402")
      (libsource (lib "eagle-import") (part "BLM15HB121SN1"))
    )
    (comp (ref "L9")
      (value "BLM15HB121SN1")
      (footprint "eagle-import:0402")
      (libsource (lib "eagle-import") (part "BLM15HB121SN1"))
    )
    (comp (ref "LOGO1")
      (value "OSHW_LOGO_FILLX0200-NT")
      (footprint "eagle-import:OSHW_FILLX200_NOTEXT")
      (libsource (lib "eagle-import") (part "OSHW_LOGO_FILLX0200-NT"))
    )
    (comp (ref "R7")
      (value "DNP")
      (footprint "eagle-import:0402-RES")
      (libsource (lib "eagle-import") (part "RESISTOR0402-RES"))
    )
    (comp (ref "R8")
      (value "0")
      (footprint "eagle-import:0402-RES")
      (libsource (lib "eagle-import") (part "RESISTOR0402-RES"))
    )
    (comp (ref "R13")
      (value "10k")
      (footprint "eagle-import:0402-RES")
      (libsource (lib "eagle-import") (part "RESISTOR0402-RES"))
    )
    (comp (ref "R16")
      (value "2.2k")
      (footprint "eagle-import:0402-RES")
      (libsource (lib "eagle-import") (part "RESISTOR0402-RES"))
    )
    (comp (ref "R17")
      (value "4K7, 1%")
      (footprint "eagle-import:R0402")
      (fields (field (name "MPN") "RC0402FR-074K7L"))
      (libsource (lib "eagle-import") (part "R-EU_R0402"))
    )
    (comp (ref "R18")
      (value "4K7, 1%")
      (footprint "eagle-import:R0402")
      (fields (field (name "MPN") "RC0402FR-074K7L"))
      (libsource (lib "eagle-import") (part "R-EU_R0402"))
    )
    (comp (ref "R22")
      (value "100")
      (footprint "eagle-import:0402-RES")
      (libsource (lib "eagle-import") (part "RESISTOR0402-RES"))
    )
    (comp (ref "R24")
      (value "100")
      (footprint "eagle-import:0402-RES")
      (libsource (lib "eagle-import") (part "RESISTOR0402-RES"))
    )
    (comp (ref "R26")
      (value "10k")
      (footprint "eagle-import:0805")
      (libsource (lib "eagle-import") (part "RESISTOR0805-RES"))
    )
    (comp (ref "R27")
      (value "10k")
      (footprint "eagle-import:0805")
      (libsource (lib "eagle-import") (part "RESISTOR0805-RES"))
    )
    (comp (ref "R39")
      (value "10K")
      (footprint "eagle-import:R0402")
      (fields (field (name "MPN") "RC0402FR-0710KL"))
      (libsource (lib "eagle-import") (part "R-EU_R0402"))
    )
    (comp (ref "R40")
      (value "10K")
      (footprint "eagle-import:R0402")
      (fields (field (name "MPN") "RC0402FR-0710KL"))
      (libsource (lib "eagle-import") (part "R-EU_R0402"))
    )
    (comp (ref "R50")
      (value "10k")
      (footprint "eagle-import:0805")
      (libsource (lib "eagle-import") (part "RESISTOR0805-RES"))
    )
    (comp (ref "R51")
      (value "10k")
      (footprint "eagle-import:0805")
      (libsource (lib "eagle-import") (part "RESISTOR0805-RES"))
    )
    (comp (ref "R52")
      (value "10k")
      (footprint "eagle-import:0805")
      (libsource (lib "eagle-import") (part "RESISTOR0805-RES"))
    )
    (comp (ref "R56")
      (value "100")
      (footprint "eagle-import:0402-RES")
      (libsource (lib "eagle-import") (part "RESISTOR0402-RES"))
    )
    (comp (ref "R58")
      (value "100")
      (footprint "eagle-import:0402-RES")
      (libsource (lib "eagle-import") (part "RESISTOR0402-RES"))
    )
    (comp (ref "R59")
      (value "10k")
      (footprint "eagle-import:0805")
      (libsource (lib "eagle-import") (part "RESISTOR0805-RES"))
    )
    (comp (ref "R60")
      (value "10k")
      (footprint "eagle-import:0805")
      (libsource (lib "eagle-import") (part "RESISTOR0805-RES"))
    )
    (comp (ref "R63")
      (value "10k")
      (footprint "eagle-import:0805")
      (libsource (lib "eagle-import") (part "RESISTOR0805-RES"))
    )
    (comp (ref "R64")
      (value "10k")
      (footprint "eagle-import:0805")
      (libsource (lib "eagle-import") (part "RESISTOR0805-RES"))
    )
    (comp (ref "R65")
      (value "10k")
      (footprint "eagle-import:0805")
      (libsource (lib "eagle-import") (part "RESISTOR0805-RES"))
    )
    (comp (ref "R68")
      (value "10k")
      (footprint "eagle-import:0402-RES")
      (libsource (lib "eagle-import") (part "RESISTOR0402-RES"))
    )
    (comp (ref "R69")
      (value "4.3k")
      (footprint "eagle-import:0402-RES")
      (libsource (lib "eagle-import") (part "RESISTOR0402-RES"))
    )
    (comp (ref "R70")
      (value "100")
      (footprint "eagle-import:0402-RES")
      (libsource (lib "eagle-import") (part "RESISTOR0402-RES"))
    )
    (comp (ref "R71")
      (value "100")
      (footprint "eagle-import:0402-RES")
      (libsource (lib "eagle-import") (part "RESISTOR0402-RES"))
    )
    (comp (ref "R72")
      (value "10k")
      (footprint "eagle-import:0805")
      (libsource (lib "eagle-import") (part "RESISTOR0805-RES"))
    )
    (comp (ref "R73")
      (value "10k")
      (footprint "eagle-import:0805")
      (libsource (lib "eagle-import") (part "RESISTOR0805-RES"))
    )
    (comp (ref "R74")
      (value "10k")
      (footprint "eagle-import:0805")
      (libsource (lib "eagle-import") (part "RESISTOR0805-RES"))
    )
    (comp (ref "R75")
      (value "10k")
      (footprint "eagle-import:0805")
      (libsource (lib "eagle-import") (part "RESISTOR0805-RES"))
    )
    (comp (ref "R76")
      (value "10k")
      (footprint "eagle-import:0805")
      (libsource (lib "eagle-import") (part "RESISTOR0805-RES"))
    )
    (comp (ref "R79")
      (value "10k")
      (footprint "eagle-import:0402-RES")
      (libsource (lib "eagle-import") (part "RESISTOR0402-RES"))
    )
    (comp (ref "R80")
      (value "7.5k")
      (footprint "eagle-import:0402-RES")
      (libsource (lib "eagle-import") (part "RESISTOR0402-RES"))
    )
    (comp (ref "R81")
      (value "100")
      (footprint "eagle-import:0402-RES")
      (libsource (lib "eagle-import") (part "RESISTOR0402-RES"))
    )
    (comp (ref "R82")
      (value "100")
      (footprint "eagle-import:0402-RES")
      (libsource (lib "eagle-import") (part "RESISTOR0402-RES"))
    )
    (comp (ref "R83")
      (value "10k")
      (footprint "eagle-import:0805")
      (libsource (lib "eagle-import") (part "RESISTOR0805-RES"))
    )
    (comp (ref "R84")
      (value "10k")
      (footprint "eagle-import:0805")
      (libsource (lib "eagle-import") (part "RESISTOR0805-RES"))
    )
    (comp (ref "R85")
      (value "10k")
      (footprint "eagle-import:0805")
      (libsource (lib "eagle-import") (part "RESISTOR0805-RES"))
    )
    (comp (ref "R86")
      (value "10k")
      (footprint "eagle-import:0805")
      (libsource (lib "eagle-import") (part "RESISTOR0805-RES"))
    )
    (comp (ref "R87")
      (value "10k")
      (footprint "eagle-import:0805")
      (libsource (lib "eagle-import") (part "RESISTOR0805-RES"))
    )
    (comp (ref "U$4")
      (value "CC-BY-SA")
      (footprint "eagle-import:CC-BY-SA")
      (libsource (lib "eagle-import") (part "CC-BY-SA"))
    )
    (comp (ref "U3")
      (value "MCP9600")
      (footprint "eagle-import:MQFN-20")
      (libsource (lib "eagle-import") (part "MCP9600"))
    )
    (comp (ref "U4")
      (value "MCP9600")
      (footprint "eagle-import:MQFN-20")
      (libsource (lib "eagle-import") (part "MCP9600"))
    )
    (comp (ref "U5")
      (value "MCP9600")
      (footprint "eagle-import:MQFN-20")
      (libsource (lib "eagle-import") (part "MCP9600"))
    )
    (comp (ref "U6")
      (value "MCP9600")
      (footprint "eagle-import:MQFN-20")
      (libsource (lib "eagle-import") (part "MCP9600"))
    )
    (comp (ref "X7")
      (value "22-05-7028-02")
      (footprint "eagle-import:7395-02")
      (fields (field (name "MPN") "640455-2"))
      (libsource (lib "eagle-import") (part "22-?-0205-7028"))
    )
    (comp (ref "X11")
      (value "22-05-7028-02")
      (footprint "eagle-import:7395-02")
      (fields (field (name "MPN") "640455-2"))
      (libsource (lib "eagle-import") (part "22-?-0205-7028"))
    )
  )
  (nets
    (net (code "1") (name "+3V3") (class "Default")
      (node (ref "3.3V") (pin "TP") (pinfunction "TP_TP") (pintype "input"))
      (node (ref "C11") (pin "1") (pinfunction "1_1") (pintype "passive"))
      (node (ref "C13") (pin "1") (pinfunction "1_1") (pintype "passive"))
      (node (ref "C2") (pin "1") (pinfunction "1_1") (pintype "passive"))
      (node (ref "C23") (pin "1") (pinfunction "1_1") (pintype "passive"))
      (node (ref "C26") (pin "1") (pinfunction "1_1") (pintype "passive"))
      (node (ref "C30") (pin "1") (pinfunction "1_1") (pintype "passive"))
      (node (ref "C33") (pin "1") (pinfunction "1_1") (pintype "passive"))
      (node (ref "C35") (pin "1") (pinfunction "1_1") (pintype "passive"))
      (node (ref "C41") (pin "1") (pinfunction "1_1") (pintype "passive"))
      (node (ref "C42") (pin "1") (pinfunction "1_1") (pintype "passive"))
      (node (ref "C5") (pin "1") (pinfunction "1_1") (pintype "passive"))
      (node (ref "C51") (pin "1") (pinfunction "1_1") (pintype "passive"))
      (node (ref "C85") (pin "1") (pinfunction "1_1") (pintype "passive"))
      (node (ref "C9") (pin "1") (pinfunction "1_1") (pintype "passive"))
      (node (ref "IC1") (pin "8") (pinfunction "8_VCC_IO_8") (pintype "bidirectional"))
      (node (ref "IC10") (pin "5") (pinfunction "VCC_5") (pintype "power_in"))
      (node (ref "IC11") (pin "5") (pinfunction "VCC_5") (pintype "power_in"))
      (node (ref "IC18") (pin "5") (pinfunction "VCC_5") (pintype "power_in"))
      (node (ref "IC2") (pin "8") (pinfunction "8_VCC_IO_8") (pintype "bidirectional"))
      (node (ref "IC3") (pin "5") (pinfunction "VCC_5") (pintype "power_in"))
      (node (ref "IC4") (pin "5") (pinfunction "VCC_5") (pintype "power_in"))
      (node (ref "IC5") (pin "5") (pinfunction "VCC_5") (pintype "power_in"))
      (node (ref "IC6") (pin "5") (pinfunction "VCC_5") (pintype "power_in"))
      (node (ref "IC7") (pin "5") (pinfunction "VCC_5") (pintype "power_in"))
      (node (ref "IC8") (pin "8") (pinfunction "8_VCC_IO_8") (pintype "bidirectional"))
      (node (ref "IC9") (pin "5") (pinfunction "VCC_5") (pintype "power_in"))
      (node (ref "P9") (pin "3") (pinfunction "3_3") (pintype "passive"))
      (node (ref "P9") (pin "4") (pinfunction "4_4") (pintype "passive"))
      (node (ref "R13") (pin "2") (pinfunction "2_2") (pintype "passive"))
      (node (ref "R23") (pin "2") (pinfunction "2_2") (pintype "passive"))
      (node (ref "R37") (pin "2") (pinfunction "2_2") (pintype "passive"))
      (node (ref "R52") (pin "1") (pinfunction "1_1") (pintype "passive"))
      (node (ref "R54") (pin "2") (pinfunction "2_2") (pintype "passive"))
      (node (ref "R63") (pin "1") (pinfunction "1_1") (pintype "passive"))
      (node (ref "R68") (pin "2") (pinfunction "2_2") (pintype "passive"))
      (node (ref "R7") (pin "2") (pinfunction "2_2") (pintype "passive"))
      (node (ref "R74") (pin "1") (pinfunction "1_1") (pintype "passive"))
      (node (ref "R79") (pin "2") (pinfunction "2_2") (pintype "passive"))
      (node (ref "R85") (pin "1") (pinfunction "1_1") (pintype "passive"))
      (node (ref "R9") (pin "2") (pinfunction "2_2") (pintype "passive"))
      (node (ref "U1") (pin "10") (pinfunction "~{SRCLR}_10") (pintype "input"))
      (node (ref "U1") (pin "16") (pinfunction "VCC_16") (pintype "power_in"))
      (node (ref "U18") (pin "1") (pinfunction "A0_1") (pintype "input"))
      (node (ref "U18") (pin "3") (pinfunction "A2_3") (pintype "input"))
      (node (ref "U18") (pin "8") (pinfunction "VCC_8") (pintype "power_in"))
      (node (ref "U2") (pin "10") (pinfunction "~{SRCLR}_10") (pintype "input"))
      (node (ref "U2") (pin "16") (pinfunction "VCC_16") (pintype "power_in"))
      (node (ref "U3") (pin "P$8") (pinfunction "VDD_P$8") (pintype "bidirectional"))
      (node (ref "U4") (pin "P$8") (pinfunction "VDD_P$8") (pintype "bidirectional"))
      (node (ref "U5") (pin "P$8") (pinfunction "VDD_P$8") (pintype "bidirectional"))
      (node (ref "U6") (pin "P$8") (pinfunction "VDD_P$8") (pintype "bidirectional"))
      (node (ref "U7") (pin "10") (pinfunction "~{SRCLR}_10") (pintype "input"))
      (node (ref "U7") (pin "16") (pinfunction "VCC_16") (pintype "power_in"))
    )
    (net (code "2") (name "DIR_A") (class "Default")
      (node (ref "IC1") (pin "7") (pinfunction "7_DIR_7") (pintype "bidirectional"))
      (node (ref "P9") (pin "29") (pinfunction "29_29") (pintype "passive"))
    )
    (net (code "3") (name "DIR_B") (class "Default")
      (node (ref "IC2") (pin "7") (pinfunction "7_DIR_7") (pintype "bidirectional"))
      (node (ref "P9") (pin "21") (pinfunction "21_21") (pintype "passive"))
    )
    (net (code "4") (name "DIR_C") (class "Default")
      (node (ref "IC8") (pin "7") (pinfunction "7_DIR_7") (pintype "bidirectional"))
      (node (ref "P9") (pin "17") (pinfunction "17_17") (pintype "passive"))
    )
    (net (code "5") (name "ENABLE") (class "Default")
      (node (ref "P9") (pin "41") (pinfunction "41_41") (pintype "passive"))
      (node (ref "R23") (pin "1") (pinfunction "1_1") (pintype "passive"))
      (node (ref "U11") (pin "23") (pinfunction "~{OE}_23") (pintype "input"))
    )
    (net (code "6") (name "ENABLE_A") (class "Default")
      (node (ref "IC1") (pin "22") (pinfunction "22_DRV_ENN_22") (pintype "bidirectional"))
      (node (ref "IC18") (pin "4") (pinfunction "O_4") (pintype "output"))
    )
    (net (code "7") (name "ENABLE_B") (class "Default")
      (node (ref "IC2") (pin "22") (pinfunction "22_DRV_ENN_22") (pintype "bidirectional"))
      (node (ref "IC7") (pin "4") (pinfunction "O_4") (pintype "output"))
    )
    (net (code "8") (name "ENABLE_C") (class "Default")
      (node (ref "IC11") (pin "4") (pinfunction "O_4") (pintype "output"))
      (node (ref "IC8") (pin "22") (pinfunction "22_DRV_ENN_22") (pintype "bidirectional"))
    )
    (net (code "9") (name "FAN4") (class "Default")
      (node (ref "R78") (pin "2") (pinfunction "2_2") (pintype "passive"))
      (node (ref "U11") (pin "13") (pinfunction "LED7_13") (pintype "output"))
    )
    (net (code "10") (name "FAN5") (class "Default")
      (node (ref "R77") (pin "2") (pinfunction "2_2") (pintype "passive"))
      (node (ref "U11") (pin "15") (pinfunction "LED8_15") (pintype "output"))
    )
    (net (code "11") (name "FAN6") (class "Default")
      (node (ref "R67") (pin "2") (pinfunction "2_2") (pintype "passive"))
      (node (ref "U11") (pin "16") (pinfunction "LED9_16") (pintype "output"))
    )
    (net (code "12") (name "FAN7") (class "Default")
      (node (ref "R66") (pin "2") (pinfunction "2_2") (pintype "passive"))
      (node (ref "U11") (pin "17") (pinfunction "LED10_17") (pintype "output"))
    )
    (net (code "13") (name "FAULT_REACH") (class "Default")
      (node (ref "C31") (pin "1") (pinfunction "1_1") (pintype "passive"))
      (node (ref "P9") (pin "37") (pinfunction "37_37") (pintype "passive"))
      (node (ref "R28") (pin "1") (pinfunction "1_1") (pintype "passive"))
      (node (ref "R29") (pin "2") (pinfunction "2_2") (pintype "passive"))
    )
    (net (code "14") (name "FAULT_X") (class "Default")
      (node (ref "IC1") (pin "20") (pinfunction "20_DIAG0_20") (pintype "bidirectional"))
      (node (ref "IC2") (pin "20") (pinfunction "20_DIAG0_20") (pintype "bidirectional"))
      (node (ref "IC8") (pin "20") (pinfunction "20_DIAG0_20") (pintype "bidirectional"))
      (node (ref "R28") (pin "2") (pinfunction "2_2") (pintype "passive"))
      (node (ref "R37") (pin "1") (pinfunction "1_1") (pintype "passive"))
      (node (ref "R54") (pin "1") (pinfunction "1_1") (pintype "passive"))
      (node (ref "R9") (pin "1") (pinfunction "1_1") (pintype "passive"))
    )
    (net (code "15") (name "GND") (class "Default")
      (node (ref "C10") (pin "2") (pinfunction "2_2") (pintype "passive"))
      (node (ref "C11") (pin "2") (pinfunction "2_2") (pintype "passive"))
      (node (ref "C12") (pin "2") (pinfunction "2_2") (pintype "passive"))
      (node (ref "C13") (pin "2") (pinfunction "2_2") (pintype "passive"))
      (node (ref "C14") (pin "1") (pinfunction "1_1") (pintype "passive"))
      (node (ref "C15") (pin "1") (pinfunction "1_1") (pintype "passive"))
      (node (ref "C17") (pin "2") (pinfunction "2_2") (pintype "passive"))
      (node (ref "C18") (pin "2") (pinfunction "2_2") (pintype "passive"))
      (node (ref "C19") (pin "2") (pinfunction "2_2") (pintype "passive"))
      (node (ref "C2") (pin "2") (pinfunction "2_2") (pintype "passive"))
      (node (ref "C20") (pin "1") (pinfunction "1_1") (pintype "passive"))
      (node (ref "C21") (pin "1") (pinfunction "1_1") (pintype "passive"))
      (node (ref "C23") (pin "2") (pinfunction "2_2") (pintype "passive"))
      (node (ref "C24") (pin "2") (pinfunction "2_2") (pintype "passive"))
      (node (ref "C25") (pin "2") (pinfunction "2_2") (pintype "passive"))
      (node (ref "C27") (pin "2") (pinfunction "2_2") (pintype "passive"))
      (node (ref "C28") (pin "-") (pinfunction "-_-") (pintype "passive"))
      (node (ref "C31") (pin "2") (pinfunction "2_2") (pintype "passive"))
      (node (ref "C33") (pin "2") (pinfunction "2_2") (pintype "passive"))
      (node (ref "C34") (pin "2") (pinfunction "2_2") (pintype "passive"))
      (node (ref "C35") (pin "2") (pinfunction "2_2") (pintype "passive"))
      (node (ref "C36") (pin "1") (pinfunction "1_1") (pintype "passive"))
      (node (ref "C37") (pin "1") (pinfunction "1_1") (pintype "passive"))
      (node (ref "C39") (pin "2") (pinfunction "2_2") (pintype "passive"))
      (node (ref "C4") (pin "2") (pinfunction "2_2") (pintype "passive"))
      (node (ref "C40") (pin "2") (pinfunction "2_2") (pintype "passive"))
      (node (ref "C41") (pin "2") (pinfunction "2_2") (pintype "passive"))
      (node (ref "C42") (pin "2") (pinfunction "2_2") (pintype "passive"))
      (node (ref "C43") (pin "2") (pinfunction "2_2") (pintype "passive"))
      (node (ref "C44") (pin "2") (pinfunction "2_2") (pintype "passive"))
      (node (ref "C45") (pin "2") (pinfunction "2_2") (pintype "passive"))
      (node (ref "C46") (pin "2") (pinfunction "2_2") (pintype "passive"))
      (node (ref "C47") (pin "2") (pinfunction "2_2") (pintype "passive"))
      (node (ref "C48") (pin "-") (pinfunction "-_-") (pintype "passive"))
      (node (ref "C5") (pin "2") (pinfunction "2_2") (pintype "passive"))
      (node (ref "C52") (pin "2") (pinfunction "2_2") (pintype "passive"))
      (node (ref "C53") (pin "2") (pinfunction "2_2") (pintype "passive"))
      (node (ref "C54") (pin "2") (pinfunction "2_2") (pintype "passive"))
      (node (ref "C57") (pin "2") (pinfunction "2_2") (pintype "passive"))
      (node (ref "C59") (pin "2") (pinfunction "2_2") (pintype "passive"))
      (node (ref "C6") (pin "2") (pinfunction "2_2") (pintype "passive"))
      (node (ref "C7") (pin "2") (pinfunction "2_2") (pintype "passive"))
      (node (ref "C71") (pin "2") (pinfunction "2_2") (pintype "passive"))
      (node (ref "C77") (pin "2") (pinfunction "2_2") (pintype "passive"))
      (node (ref "C8") (pin "-") (pinfunction "-_-") (pintype "passive"))
      (node (ref "C81") (pin "2") (pinfunction "2_2") (pintype "passive"))
      (node (ref "C85") (pin "2") (pinfunction "2_2") (pintype "passive"))
      (node (ref "D4") (pin "A") (pinfunction "A_A") (pintype "passive"))
      (node (ref "D5") (pin "A") (pinfunction "A_A") (pintype "passive"))
      (node (ref "IC1") (pin "1") (pinfunction "1_CLK_1") (pintype "bidirectional"))
      (node (ref "IC1") (pin "10") (pinfunction "10_SPI_MODE_10") (pintype "bidirectional"))
      (node (ref "IC1") (pin "12") (pinfunction "12_GNDP_12") (pintype "bidirectional"))
      (node (ref "IC1") (pin "24") (pinfunction "24_GNDA_24") (pintype "bidirectional"))
      (node (ref "IC1") (pin "35") (pinfunction "35_GNDP_35") (pintype "bidirectional"))
      (node (ref "IC1") (pin "36") (pinfunction "36_TST_MODE_36") (pintype "bidirectional"))
      (node (ref "IC1") (pin "TP") (pinfunction "PAD_TP") (pintype "bidirectional"))
      (node (ref "IC10") (pin "3") (pinfunction "GND_3") (pintype "power_in"))
      (node (ref "IC11") (pin "3") (pinfunction "GND_3") (pintype "power_in"))
      (node (ref "IC18") (pin "3") (pinfunction "GND_3") (pintype "power_in"))
      (node (ref "IC2") (pin "1") (pinfunction "1_CLK_1") (pintype "bidirectional"))
      (node (ref "IC2") (pin "10") (pinfunction "10_SPI_MODE_10") (pintype "bidirectional"))
      (node (ref "IC2") (pin "12") (pinfunction "12_GNDP_12") (pintype "bidirectional"))
      (node (ref "IC2") (pin "24") (pinfunction "24_GNDA_24") (pintype "bidirectional"))
      (node (ref "IC2") (pin "35") (pinfunction "35_GNDP_35") (pintype "bidirectional"))
      (node (ref "IC2") (pin "36") (pinfunction "36_TST_MODE_36") (pintype "bidirectional"))
      (node (ref "IC2") (pin "TP") (pinfunction "PAD_TP") (pintype "bidirectional"))
      (node (ref "IC3") (pin "3") (pinfunction "GND_3") (pintype "power_in"))
      (node (ref "IC4") (pin "3") (pinfunction "GND_3") (pintype "power_in"))
      (node (ref "IC5") (pin "3") (pinfunction "GND_3") (pintype "power_in"))
      (node (ref "IC6") (pin "3") (pinfunction "GND_3") (pintype "power_in"))
      (node (ref "IC7") (pin "3") (pinfunction "GND_3") (pintype "power_in"))
      (node (ref "IC8") (pin "1") (pinfunction "1_CLK_1") (pintype "bidirectional"))
      (node (ref "IC8") (pin "10") (pinfunction "10_SPI_MODE_10") (pintype "bidirectional"))
      (node (ref "IC8") (pin "12") (pinfunction "12_GNDP_12") (pintype "bidirectional"))
      (node (ref "IC8") (pin "24") (pinfunction "24_GNDA_24") (pintype "bidirectional"))
      (node (ref "IC8") (pin "35") (pinfunction "35_GNDP_35") (pintype "bidirectional"))
      (node (ref "IC8") (pin "36") (pinfunction "36_TST_MODE_36") (pintype "bidirectional"))
      (node (ref "IC8") (pin "TP") (pinfunction "PAD_TP") (pintype "bidirectional"))
      (node (ref "IC9") (pin "3") (pinfunction "GND_3") (pintype "power_in"))
      (node (ref "JP10") (pin "1") (pinfunction "1_1") (pintype "passive"))
      (node (ref "JP11") (pin "1") (pinfunction "1_1") (pintype "passive"))
      (node (ref "JP12") (pin "1") (pinfunction "1_1") (pintype "passive"))
      (node (ref "JP13") (pin "1") (pinfunction "1_1") (pintype "passive"))
      (node (ref "JP14") (pin "1") (pinfunction "1_1") (pintype "passive"))
      (node (ref "JP3") (pin "1") (pinfunction "1_1") (pintype "passive"))
      (node (ref "JP5") (pin "1") (pinfunction "1_1") (pintype "passive"))
      (node (ref "JP6") (pin "1") (pinfunction "1_1") (pintype "passive"))
      (node (ref "JP7") (pin "1") (pinfunction "1_1") (pintype "passive"))
      (node (ref "JP8") (pin "1") (pinfunction "1_1") (pintype "passive"))
      (node (ref "JP9") (pin "1") (pinfunction "1_1") (pintype "passive"))
      (node (ref "LED4") (pin "C") (pinfunction "C_C") (pintype "passive"))
      (node (ref "P8") (pin "1") (pinfunction "1_1") (pintype "passive"))
      (node (ref "P8") (pin "2") (pinfunction "2_2") (pintype "passive"))
      (node (ref "P9") (pin "1") (pinfunction "1_1") (pintype "passive"))
      (node (ref "P9") (pin "2") (pinfunction "2_2") (pintype "passive"))
      (node (ref "P9") (pin "43") (pinfunction "43_43") (pintype "passive"))
      (node (ref "P9") (pin "44") (pinfunction "44_44") (pintype "passive"))
      (node (ref "P9") (pin "45") (pinfunction "45_45") (pintype "passive"))
      (node (ref "P9") (pin "46") (pinfunction "46_46") (pintype "passive"))
      (node (ref "Q1") (pin "2") (pinfunction "E_2") (pintype "passive"))
      (node (ref "Q2") (pin "1") (pinfunction "S_1") (pintype "passive"))
      (node (ref "Q2") (pin "2") (pinfunction "S_2") (pintype "passive"))
      (node (ref "Q2") (pin "3") (pinfunction "S_3") (pintype "passive"))
      (node (ref "Q3") (pin "1") (pinfunction "S_1") (pintype "passive"))
      (node (ref "Q3") (pin "2") (pinfunction "S_2") (pintype "passive"))
      (node (ref "Q3") (pin "3") (pinfunction "S_3") (pintype "passive"))
      (node (ref "Q4") (pin "2") (pinfunction "E_2") (pintype "passive"))
      (node (ref "Q5") (pin "2") (pinfunction "E_2") (pintype "passive"))
      (node (ref "Q6") (pin "2") (pinfunction "E_2") (pintype "passive"))
      (node (ref "R1") (pin "1") (pinfunction "1_1") (pintype "passive"))
      (node (ref "R19") (pin "1") (pinfunction "1_1") (pintype "passive"))
      (node (ref "R2") (pin "1") (pinfunction "1_1") (pintype "passive"))
      (node (ref "R21") (pin "1") (pinfunction "1_1") (pintype "passive"))
      (node (ref "R3") (pin "1") (pinfunction "1_1") (pintype "passive"))
      (node (ref "R30") (pin "1") (pinfunction "1_1") (pintype "passive"))
      (node (ref "R31") (pin "1") (pinfunction "1_1") (pintype "passive"))
      (node (ref "R33") (pin "1") (pinfunction "1_1") (pintype "passive"))
      (node (ref "R34") (pin "1") (pinfunction "1_1") (pintype "passive"))
      (node (ref "R35") (pin "1") (pinfunction "1_1") (pintype "passive"))
      (node (ref "R4") (pin "1") (pinfunction "1_1") (pintype "passive"))
      (node (ref "R43") (pin "2") (pinfunction "2_2") (pintype "passive"))
      (node (ref "R44") (pin "2") (pinfunction "2_2") (pintype "passive"))
      (node (ref "R47") (pin "1") (pinfunction "1_1") (pintype "passive"))
      (node (ref "R48") (pin "1") (pinfunction "1_1") (pintype "passive"))
      (node (ref "U1") (pin "13") (pinfunction "~{OE}_13") (pintype "input"))
      (node (ref "U1") (pin "8") (pinfunction "GND_8") (pintype "passive"))
      (node (ref "U10") (pin "6") (pinfunction "GND_6") (pintype "power_in"))
      (node (ref "U10") (pin "EP") (pinfunction "EP_EP") (pintype "power_in"))
      (node (ref "U11") (pin "14") (pinfunction "VSS_14") (pintype "passive"))
      (node (ref "U11") (pin "24") (pinfunction "A5_24") (pintype "input"))
      (node (ref "U18") (pin "2") (pinfunction "A1_2") (pintype "input"))
      (node (ref "U18") (pin "4") (pinfunction "GND_4") (pintype "power_in"))
      (node (ref "U2") (pin "13") (pinfunction "~{OE}_13") (pintype "input"))
      (node (ref "U2") (pin "8") (pinfunction "GND_8") (pintype "passive"))
      (node (ref "U7") (pin "13") (pinfunction "~{OE}_13") (pintype "input"))
      (node (ref "U7") (pin "8") (pinfunction "GND_8") (pintype "passive"))
      (node (ref "X11") (pin "1") (pinfunction "S_1") (pintype "passive"))
      (node (ref "X2") (pin "1") (pinfunction "1_1") (pintype "passive"))
      (node (ref "X2") (pin "2") (pinfunction "1_2") (pintype "passive"))
      (node (ref "X7") (pin "1") (pinfunction "S_1") (pintype "passive"))
    )
    (net (code "16") (name "GNDI") (class "Default")
      (node (ref "C26") (pin "2") (pinfunction "2_2") (pintype "passive"))
      (node (ref "C30") (pin "2") (pinfunction "2_2") (pintype "passive"))
      (node (ref "C51") (pin "2") (pinfunction "2_2") (pintype "passive"))
      (node (ref "C9") (pin "2") (pinfunction "2_2") (pintype "passive"))
      (node (ref "JP10") (pin "2") (pinfunction "2_2") (pintype "passive"))
      (node (ref "JP11") (pin "2") (pinfunction "2_2") (pintype "passive"))
      (node (ref "JP12") (pin "2") (pinfunction "2_2") (pintype "passive"))
      (node (ref "JP13") (pin "2") (pinfunction "2_2") (pintype "passive"))
      (node (ref "JP14") (pin "2") (pinfunction "2_2") (pintype "passive"))
      (node (ref "JP3") (pin "2") (pinfunction "2_2") (pintype "passive"))
      (node (ref "JP5") (pin "2") (pinfunction "2_2") (pintype "passive"))
      (node (ref "JP6") (pin "2") (pinfunction "2_2") (pintype "passive"))
      (node (ref "JP7") (pin "2") (pinfunction "2_2") (pintype "passive"))
      (node (ref "JP8") (pin "2") (pinfunction "2_2") (pintype "passive"))
      (node (ref "JP9") (pin "2") (pinfunction "2_2") (pintype "passive"))
      (node (ref "R16") (pin "1") (pinfunction "1_1") (pintype "passive"))
      (node (ref "R26") (pin "2") (pinfunction "2_2") (pintype "passive"))
      (node (ref "R50") (pin "2") (pinfunction "2_2") (pintype "passive"))
      (node (ref "R60") (pin "1") (pinfunction "1_1") (pintype "passive"))
      (node (ref "R65") (pin "1") (pinfunction "1_1") (pintype "passive"))
      (node (ref "R69") (pin "1") (pinfunction "1_1") (pintype "passive"))
      (node (ref "R72") (pin "2") (pinfunction "2_2") (pintype "passive"))
      (node (ref "R76") (pin "1") (pinfunction "1_1") (pintype "passive"))
      (node (ref "R8") (pin "1") (pinfunction "1_1") (pintype "passive"))
      (node (ref "R80") (pin "1") (pinfunction "1_1") (pintype "passive"))
      (node (ref "R83") (pin "2") (pinfunction "2_2") (pintype "passive"))
      (node (ref "R87") (pin "1") (pinfunction "1_1") (pintype "passive"))
      (node (ref "U3") (pin "P$1") (pinfunction "GND_P$1") (pintype "bidirectional"))
      (node (ref "U3") (pin "P$10") (pinfunction "GND10_P$10") (pintype "bidirectional"))
      (node (ref "U3") (pin "P$13") (pinfunction "GND13_P$13") (pintype "bidirectional"))
      (node (ref "U3") (pin "P$17") (pinfunction "GND17_P$17") (pintype "bidirectional"))
      (node (ref "U3") (pin "P$18") (pinfunction "GND18_P$18") (pintype "bidirectional"))
      (node (ref "U3") (pin "P$21") (pinfunction "PAD_P$21") (pintype "bidirectional"))
      (node (ref "U3") (pin "P$3") (pinfunction "GND3_P$3") (pintype "bidirectional"))
      (node (ref "U3") (pin "P$5") (pinfunction "GND5_P$5") (pintype "bidirectional"))
      (node (ref "U3") (pin "P$6") (pinfunction "GND6_P$6") (pintype "bidirectional"))
      (node (ref "U3") (pin "P$7") (pinfunction "GND7_P$7") (pintype "bidirectional"))
      (node (ref "U3") (pin "P$9") (pinfunction "GND9_P$9") (pintype "bidirectional"))
      (node (ref "U4") (pin "P$1") (pinfunction "GND_P$1") (pintype "bidirectional"))
      (node (ref "U4") (pin "P$10") (pinfunction "GND10_P$10") (pintype "bidirectional"))
      (node (ref "U4") (pin "P$13") (pinfunction "GND13_P$13") (pintype "bidirectional"))
      (node (ref "U4") (pin "P$17") (pinfunction "GND17_P$17") (pintype "bidirectional"))
      (node (ref "U4") (pin "P$18") (pinfunction "GND18_P$18") (pintype "bidirectional"))
      (node (ref "U4") (pin "P$21") (pinfunction "PAD_P$21") (pintype "bidirectional"))
      (node (ref "U4") (pin "P$3") (pinfunction "GND3_P$3") (pintype "bidirectional"))
      (node (ref "U4") (pin "P$5") (pinfunction "GND5_P$5") (pintype "bidirectional"))
      (node (ref "U4") (pin "P$6") (pinfunction "GND6_P$6") (pintype "bidirectional"))
      (node (ref "U4") (pin "P$7") (pinfunction "GND7_P$7") (pintype "bidirectional"))
      (node (ref "U4") (pin "P$9") (pinfunction "GND9_P$9") (pintype "bidirectional"))
      (node (ref "U5") (pin "P$1") (pinfunction "GND_P$1") (pintype "bidirectional"))
      (node (ref "U5") (pin "P$10") (pinfunction "GND10_P$10") (pintype "bidirectional"))
      (node (ref "U5") (pin "P$13") (pinfunction "GND13_P$13") (pintype "bidirectional"))
      (node (ref "U5") (pin "P$17") (pinfunction "GND17_P$17") (pintype "bidirectional"))
      (node (ref "U5") (pin "P$18") (pinfunction "GND18_P$18") (pintype "bidirectional"))
      (node (ref "U5") (pin "P$21") (pinfunction "PAD_P$21") (pintype "bidirectional"))
      (node (ref "U5") (pin "P$3") (pinfunction "GND3_P$3") (pintype "bidirectional"))
      (node (ref "U5") (pin "P$5") (pinfunction "GND5_P$5") (pintype "bidirectional"))
      (node (ref "U5") (pin "P$6") (pinfunction "GND6_P$6") (pintype "bidirectional"))
      (node (ref "U5") (pin "P$7") (pinfunction "GND7_P$7") (pintype "bidirectional"))
      (node (ref "U5") (pin "P$9") (pinfunction "GND9_P$9") (pintype "bidirectional"))
      (node (ref "U6") (pin "P$1") (pinfunction "GND_P$1") (pintype "bidirectional"))
      (node (ref "U6") (pin "P$10") (pinfunction "GND10_P$10") (pintype "bidirectional"))
      (node (ref "U6") (pin "P$13") (pinfunction "GND13_P$13") (pintype "bidirectional"))
      (node (ref "U6") (pin "P$17") (pinfunction "GND17_P$17") (pintype "bidirectional"))
      (node (ref "U6") (pin "P$18") (pinfunction "GND18_P$18") (pintype "bidirectional"))
      (node (ref "U6") (pin "P$21") (pinfunction "PAD_P$21") (pintype "bidirectional"))
      (node (ref "U6") (pin "P$3") (pinfunction "GND3_P$3") (pintype "bidirectional"))
      (node (ref "U6") (pin "P$5") (pinfunction "GND5_P$5") (pintype "bidirectional"))
      (node (ref "U6") (pin "P$6") (pinfunction "GND6_P$6") (pintype "bidirectional"))
      (node (ref "U6") (pin "P$7") (pinfunction "GND7_P$7") (pintype "bidirectional"))
      (node (ref "U6") (pin "P$9") (pinfunction "GND9_P$9") (pintype "bidirectional"))
    )
    (net (code "17") (name "HEATER_A") (class "Default")
      (node (ref "R61") (pin "2") (pinfunction "2_2") (pintype "passive"))
      (node (ref "U11") (pin "9") (pinfunction "LED3_9") (pintype "output"))
    )
    (net (code "18") (name "HEATER_B") (class "Default")
      (node (ref "R62") (pin "2") (pinfunction "2_2") (pintype "passive"))
      (node (ref "U11") (pin "11") (pinfunction "LED5_11") (pintype "output"))
    )
    (net (code "19") (name "I2C2_SCL") (class "Default")
      (node (ref "P9") (pin "19") (pinfunction "19_19") (pintype "passive"))
      (node (ref "U11") (pin "26") (pinfunction "SCL_26") (pintype "input"))
      (node (ref "U18") (pin "6") (pinfunction "SCL_6") (pintype "input"))
      (node (ref "U3") (pin "P$19") (pinfunction "SCL_P$19") (pintype "bidirectional"))
      (node (ref "U4") (pin "P$19") (pinfunction "SCL_P$19") (pintype "bidirectional"))
      (node (ref "U5") (pin "P$19") (pinfunction "SCL_P$19") (pintype "bidirectional"))
      (node (ref "U6") (pin "P$19") (pinfunction "SCL_P$19") (pintype "bidirectional"))
    )
    (net (code "20") (name "I2C2_SDA") (class "Default")
      (node (ref "P9") (pin "20") (pinfunction "20_20") (pintype "passive"))
      (node (ref "U11") (pin "27") (pinfunction "SDA_27") (pintype "bidirectional"))
      (node (ref "U18") (pin "5") (pinfunction "SDA_5") (pintype "bidirectional"))
      (node (ref "U3") (pin "P$20") (pinfunction "SDA_P$20") (pintype "bidirectional"))
      (node (ref "U4") (pin "P$20") (pinfunction "SDA_P$20") (pintype "bidirectional"))
      (node (ref "U5") (pin "P$20") (pinfunction "SDA_P$20") (pintype "bidirectional"))
      (node (ref "U6") (pin "P$20") (pinfunction "SDA_P$20") (pintype "bidirectional"))
    )
    (net (code "21") (name "IREF_A_RAW") (class "Default")
      (node (ref "R41") (pin "2") (pinfunction "2_2") (pintype "passive"))
      (node (ref "U11") (pin "18") (pinfunction "LED11_18") (pintype "output"))
    )
    (net (code "22") (name "IREF_B_RAW") (class "Default")
      (node (ref "R12") (pin "2") (pinfunction "2_2") (pintype "passive"))
      (node (ref "U11") (pin "19") (pinfunction "LED12_19") (pintype "output"))
    )
    (net (code "23") (name "IREF_C_RAW") (class "Default")
      (node (ref "R46") (pin "2") (pinfunction "2_2") (pintype "passive"))
      (node (ref "U11") (pin "20") (pinfunction "LED13_20") (pintype "output"))
    )
    (net (code "24") (name "Net-(C19-Pad1)") (class "Default")
      (node (ref "C19") (pin "1") (pinfunction "1_1") (pintype "passive"))
      (node (ref "R12") (pin "1") (pinfunction "1_1") (pintype "passive"))
      (node (ref "R6") (pin "2") (pinfunction "2_2") (pintype "passive"))
    )
    (net (code "25") (name "Net-(C40-Pad1)") (class "Default")
      (node (ref "C40") (pin "1") (pinfunction "1_1") (pintype "passive"))
      (node (ref "R36") (pin "2") (pinfunction "2_2") (pintype "passive"))
      (node (ref "R46") (pin "1") (pinfunction "1_1") (pintype "passive"))
    )
    (net (code "26") (name "Net-(C56-Pad2)") (class "Default")
      (node (ref "C56") (pin "2") (pinfunction "2_2") (pintype "passive"))
      (node (ref "R44") (pin "1") (pinfunction "1_1") (pintype "passive"))
    )
    (net (code "27") (name "Net-(C77-Pad1)") (class "Default")
      (node (ref "C77") (pin "1") (pinfunction "1_1") (pintype "passive"))
      (node (ref "R41") (pin "1") (pinfunction "1_1") (pintype "passive"))
      (node (ref "R49") (pin "2") (pinfunction "2_2") (pintype "passive"))
    )
    (net (code "28") (name "Net-(IC1-3_SCK_CFG2)") (class "Default")
      (node (ref "IC1") (pin "3") (pinfunction "3_SCK_CFG2_3") (pintype "bidirectional"))
      (node (ref "IC3") (pin "4") (pinfunction "O_4") (pintype "output"))
    )
    (net (code "29") (name "Net-(IC1-4_SDI_CFG1)") (class "Default")
      (node (ref "IC1") (pin "4") (pinfunction "4_SDI_CFG1_4") (pintype "bidirectional"))
      (node (ref "IC4") (pin "4") (pinfunction "O_4") (pintype "output"))
    )
    (net (code "30") (name "Net-(IC1-5_SD0_CFG0)") (class "Default")
      (node (ref "IC1") (pin "5") (pinfunction "5_SD0_CFG0_5") (pintype "bidirectional"))
      (node (ref "U1") (pin "3") (pinfunction "QD_3") (pintype "output"))
    )
    (net (code "31") (name "Net-(IC1-13_OB1)") (class "Default")
      (node (ref "IC1") (pin "13") (pinfunction "13_OB1_13") (pintype "bidirectional"))
      (node (ref "X14") (pin "3") (pinfunction "S_3") (pintype "passive"))
    )
    (net (code "32") (name "Net-(IC1-14_BRB)") (class "Default")
      (node (ref "IC1") (pin "14") (pinfunction "14_BRB_14") (pintype "bidirectional"))
      (node (ref "R1") (pin "2") (pinfunction "2_2") (pintype "passive"))
    )
    (net (code "33") (name "Net-(IC1-15_OB2)") (class "Default")
      (node (ref "IC1") (pin "15") (pinfunction "15_OB2_15") (pintype "bidirectional"))
      (node (ref "X14") (pin "4") (pinfunction "S_4") (pintype "passive"))
    )
    (net (code "34") (name "Net-(IC1-18_DCEN_CFG4)") (class "Default")
      (node (ref "IC1") (pin "18") (pinfunction "18_DCEN_CFG4_18") (pintype "bidirectional"))
      (node (ref "U1") (pin "2") (pinfunction "QC_2") (pintype "output"))
    )
    (net (code "35") (name "Net-(IC1-19_DCIN_CFG5)") (class "Default")
      (node (ref "IC1") (pin "19") (pinfunction "19_DCIN_CFG5_19") (pintype "bidirectional"))
      (node (ref "U1") (pin "1") (pinfunction "QB_1") (pintype "output"))
    )
    (net (code "36") (name "Net-(IC1-23_AIN_IREF)") (class "Default")
      (node (ref "C12") (pin "1") (pinfunction "1_1") (pintype "passive"))
      (node (ref "IC1") (pin "23") (pinfunction "23_AIN_IREF_23") (pintype "bidirectional"))
      (node (ref "R49") (pin "1") (pinfunction "1_1") (pintype "passive"))
    )
    (net (code "37") (name "Net-(IC1-25_5VOUT)") (class "Default")
      (node (ref "C21") (pin "2") (pinfunction "2_2") (pintype "passive"))
      (node (ref "IC1") (pin "25") (pinfunction "25_5VOUT_25") (pintype "bidirectional"))
      (node (ref "R53") (pin "1") (pinfunction "1_1") (pintype "passive"))
    )
    (net (code "38") (name "Net-(IC1-26_VCC)") (class "Default")
      (node (ref "C71") (pin "1") (pinfunction "1_1") (pintype "passive"))
      (node (ref "IC1") (pin "26") (pinfunction "26_VCC_26") (pintype "bidirectional"))
      (node (ref "R53") (pin "2") (pinfunction "2_2") (pintype "passive"))
    )
    (net (code "39") (name "Net-(IC1-27_CP0)") (class "Default")
      (node (ref "C1") (pin "2") (pinfunction "2_2") (pintype "passive"))
      (node (ref "IC1") (pin "27") (pinfunction "27_CP0_27") (pintype "bidirectional"))
    )
    (net (code "40") (name "Net-(IC1-28_CPI)") (class "Default")
      (node (ref "C1") (pin "1") (pinfunction "1_1") (pintype "passive"))
      (node (ref "IC1") (pin "28") (pinfunction "28_CPI_28") (pintype "bidirectional"))
    )
    (net (code "41") (name "Net-(IC1-29_VCP)") (class "Default")
      (node (ref "C22") (pin "1") (pinfunction "1_1") (pintype "passive"))
      (node (ref "IC1") (pin "29") (pinfunction "29_VCP_29") (pintype "bidirectional"))
    )
    (net (code "42") (name "Net-(IC1-32_OA2)") (class "Default")
      (node (ref "IC1") (pin "32") (pinfunction "32_OA2_32") (pintype "bidirectional"))
      (node (ref "X14") (pin "1") (pinfunction "S_1") (pintype "passive"))
    )
    (net (code "43") (name "Net-(IC1-33_BRA)") (class "Default")
      (node (ref "IC1") (pin "33") (pinfunction "33_BRA_33") (pintype "bidirectional"))
      (node (ref "R2") (pin "2") (pinfunction "2_2") (pintype "passive"))
    )
    (net (code "44") (name "Net-(IC1-34_OA1)") (class "Default")
      (node (ref "IC1") (pin "34") (pinfunction "34_OA1_34") (pintype "bidirectional"))
      (node (ref "X14") (pin "2") (pinfunction "S_2") (pintype "passive"))
    )
    (net (code "45") (name "Net-(IC2-3_SCK_CFG2)") (class "Default")
      (node (ref "IC2") (pin "3") (pinfunction "3_SCK_CFG2_3") (pintype "bidirectional"))
      (node (ref "IC5") (pin "4") (pinfunction "O_4") (pintype "output"))
    )
    (net (code "46") (name "Net-(IC2-4_SDI_CFG1)") (class "Default")
      (node (ref "IC2") (pin "4") (pinfunction "4_SDI_CFG1_4") (pintype "bidirectional"))
      (node (ref "IC6") (pin "4") (pinfunction "O_4") (pintype "output"))
    )
    (net (code "47") (name "Net-(IC2-5_SD0_CFG0)") (class "Default")
      (node (ref "IC2") (pin "5") (pinfunction "5_SD0_CFG0_5") (pintype "bidirectional"))
      (node (ref "U2") (pin "3") (pinfunction "QD_3") (pintype "output"))
    )
    (net (code "48") (name "Net-(IC2-13_OB1)") (class "Default")
      (node (ref "IC2") (pin "13") (pinfunction "13_OB1_13") (pintype "bidirectional"))
      (node (ref "X6") (pin "3") (pinfunction "S_3") (pintype "passive"))
    )
    (net (code "49") (name "Net-(IC2-14_BRB)") (class "Default")
      (node (ref "IC2") (pin "14") (pinfunction "14_BRB_14") (pintype "bidirectional"))
      (node (ref "R3") (pin "2") (pinfunction "2_2") (pintype "passive"))
    )
    (net (code "50") (name "Net-(IC2-15_OB2)") (class "Default")
      (node (ref "IC2") (pin "15") (pinfunction "15_OB2_15") (pintype "bidirectional"))
      (node (ref "X6") (pin "4") (pinfunction "S_4") (pintype "passive"))
    )
    (net (code "51") (name "Net-(IC2-18_DCEN_CFG4)") (class "Default")
      (node (ref "IC2") (pin "18") (pinfunction "18_DCEN_CFG4_18") (pintype "bidirectional"))
      (node (ref "U2") (pin "2") (pinfunction "QC_2") (pintype "output"))
    )
    (net (code "52") (name "Net-(IC2-19_DCIN_CFG5)") (class "Default")
      (node (ref "IC2") (pin "19") (pinfunction "19_DCIN_CFG5_19") (pintype "bidirectional"))
      (node (ref "U2") (pin "1") (pinfunction "QB_1") (pintype "output"))
    )
    (net (code "53") (name "Net-(IC2-23_AIN_IREF)") (class "Default")
      (node (ref "C10") (pin "1") (pinfunction "1_1") (pintype "passive"))
      (node (ref "IC2") (pin "23") (pinfunction "23_AIN_IREF_23") (pintype "bidirectional"))
      (node (ref "R6") (pin "1") (pinfunction "1_1") (pintype "passive"))
    )
    (net (code "54") (name "Net-(IC2-25_5VOUT)") (class "Default")
      (node (ref "C15") (pin "2") (pinfunction "2_2") (pintype "passive"))
      (node (ref "IC2") (pin "25") (pinfunction "25_5VOUT_25") (pintype "bidirectional"))
      (node (ref "R10") (pin "1") (pinfunction "1_1") (pintype "passive"))
    )
    (net (code "55") (name "Net-(IC2-26_VCC)") (class "Default")
      (node (ref "C18") (pin "1") (pinfunction "1_1") (pintype "passive"))
      (node (ref "IC2") (pin "26") (pinfunction "26_VCC_26") (pintype "bidirectional"))
      (node (ref "R10") (pin "2") (pinfunction "2_2") (pintype "passive"))
    )
    (net (code "56") (name "Net-(IC2-27_CP0)") (class "Default")
      (node (ref "C3") (pin "2") (pinfunction "2_2") (pintype "passive"))
      (node (ref "IC2") (pin "27") (pinfunction "27_CP0_27") (pintype "bidirectional"))
    )
    (net (code "57") (name "Net-(IC2-28_CPI)") (class "Default")
      (node (ref "C3") (pin "1") (pinfunction "1_1") (pintype "passive"))
      (node (ref "IC2") (pin "28") (pinfunction "28_CPI_28") (pintype "bidirectional"))
    )
    (net (code "58") (name "Net-(IC2-29_VCP)") (class "Default")
      (node (ref "C16") (pin "1") (pinfunction "1_1") (pintype "passive"))
      (node (ref "IC2") (pin "29") (pinfunction "29_VCP_29") (pintype "bidirectional"))
    )
    (net (code "59") (name "Net-(IC2-32_OA2)") (class "Default")
      (node (ref "IC2") (pin "32") (pinfunction "32_OA2_32") (pintype "bidirectional"))
      (node (ref "X6") (pin "1") (pinfunction "S_1") (pintype "passive"))
    )
    (net (code "60") (name "Net-(IC2-33_BRA)") (class "Default")
      (node (ref "IC2") (pin "33") (pinfunction "33_BRA_33") (pintype "bidirectional"))
      (node (ref "R4") (pin "2") (pinfunction "2_2") (pintype "passive"))
    )
    (net (code "61") (name "Net-(IC2-34_OA1)") (class "Default")
      (node (ref "IC2") (pin "34") (pinfunction "34_OA1_34") (pintype "bidirectional"))
      (node (ref "X6") (pin "2") (pinfunction "S_2") (pintype "passive"))
    )
    (net (code "62") (name "Net-(IC3A-I)") (class "Default")
      (node (ref "IC3") (pin "2") (pinfunction "I_2") (pintype "input"))
      (node (ref "U1") (pin "4") (pinfunction "QE_4") (pintype "output"))
    )
    (net (code "63") (name "Net-(IC3A-OE)") (class "Default")
      (node (ref "IC3") (pin "1") (pinfunction "OE_1") (pintype "input"))
      (node (ref "U1") (pin "5") (pinfunction "QF_5") (pintype "output"))
    )
    (net (code "64") (name "Net-(IC4A-I)") (class "Default")
      (node (ref "IC4") (pin "2") (pinfunction "I_2") (pintype "input"))
      (node (ref "U1") (pin "6") (pinfunction "QG_6") (pintype "output"))
    )
    (net (code "65") (name "Net-(IC4A-OE)") (class "Default")
      (node (ref "IC4") (pin "1") (pinfunction "OE_1") (pintype "input"))
      (node (ref "U1") (pin "7") (pinfunction "QH_7") (pintype "output"))
    )
    (net (code "66") (name "Net-(IC5A-I)") (class "Default")
      (node (ref "IC5") (pin "2") (pinfunction "I_2") (pintype "input"))
      (node (ref "U2") (pin "4") (pinfunction "QE_4") (pintype "output"))
    )
    (net (code "67") (name "Net-(IC5A-OE)") (class "Default")
      (node (ref "IC5") (pin "1") (pinfunction "OE_1") (pintype "input"))
      (node (ref "U2") (pin "5") (pinfunction "QF_5") (pintype "output"))
    )
    (net (code "68") (name "Net-(IC6A-I)") (class "Default")
      (node (ref "IC6") (pin "2") (pinfunction "I_2") (pintype "input"))
      (node (ref "U2") (pin "6") (pinfunction "QG_6") (pintype "output"))
    )
    (net (code "69") (name "Net-(IC6A-OE)") (class "Default")
      (node (ref "IC6") (pin "1") (pinfunction "OE_1") (pintype "input"))
      (node (ref "U2") (pin "7") (pinfunction "QH_7") (pintype "output"))
    )
    (net (code "70") (name "Net-(IC7A-I)") (class "Default")
      (node (ref "IC7") (pin "2") (pinfunction "I_2") (pintype "input"))
      (node (ref "U2") (pin "15") (pinfunction "QA_15") (pintype "output"))
    )
    (net (code "71") (name "Net-(IC8-3_SCK_CFG2)") (class "Default")
      (node (ref "IC8") (pin "3") (pinfunction "3_SCK_CFG2_3") (pintype "bidirectional"))
      (node (ref "IC9") (pin "4") (pinfunction "O_4") (pintype "output"))
    )
    (net (code "72") (name "Net-(IC8-5_SD0_CFG0)") (class "Default")
      (node (ref "IC8") (pin "5") (pinfunction "5_SD0_CFG0_5") (pintype "bidirectional"))
      (node (ref "U7") (pin "3") (pinfunction "QD_3") (pintype "output"))
    )
    (net (code "73") (name "Net-(IC8-13_OB1)") (class "Default")
      (node (ref "IC8") (pin "13") (pinfunction "13_OB1_13") (pintype "bidirectional"))
      (node (ref "X8") (pin "3") (pinfunction "S_3") (pintype "passive"))
    )
    (net (code "74") (name "Net-(IC8-14_BRB)") (class "Default")
      (node (ref "IC8") (pin "14") (pinfunction "14_BRB_14") (pintype "bidirectional"))
      (node (ref "R31") (pin "2") (pinfunction "2_2") (pintype "passive"))
    )
    (net (code "75") (name "Net-(IC8-15_OB2)") (class "Default")
      (node (ref "IC8") (pin "15") (pinfunction "15_OB2_15") (pintype "bidirectional"))
      (node (ref "X8") (pin "4") (pinfunction "S_4") (pintype "passive"))
    )
    (net (code "76") (name "Net-(IC8-18_DCEN_CFG4)") (class "Default")
      (node (ref "IC8") (pin "18") (pinfunction "18_DCEN_CFG4_18") (pintype "bidirectional"))
      (node (ref "U7") (pin "2") (pinfunction "QC_2") (pintype "output"))
    )
    (net (code "77") (name "Net-(IC8-19_DCIN_CFG5)") (class "Default")
      (node (ref "IC8") (pin "19") (pinfunction "19_DCIN_CFG5_19") (pintype "bidirectional"))
      (node (ref "U7") (pin "1") (pinfunction "QB_1") (pintype "output"))
    )
    (net (code "78") (name "Net-(IC8-23_AIN_IREF)") (class "Default")
      (node (ref "C34") (pin "1") (pinfunction "1_1") (pintype "passive"))
      (node (ref "IC8") (pin "23") (pinfunction "23_AIN_IREF_23") (pintype "bidirectional"))
      (node (ref "R36") (pin "1") (pinfunction "1_1") (pintype "passive"))
    )
    (net (code "79") (name "Net-(IC8-25_5VOUT)") (class "Default")
      (node (ref "C37") (pin "2") (pinfunction "2_2") (pintype "passive"))
      (node (ref "IC8") (pin "25") (pinfunction "25_5VOUT_25") (pintype "bidirectional"))
      (node (ref "R38") (pin "1") (pinfunction "1_1") (pintype "passive"))
    )
    (net (code "80") (name "Net-(IC8-26_VCC)") (class "Default")
      (node (ref "C39") (pin "1") (pinfunction "1_1") (pintype "passive"))
      (node (ref "IC8") (pin "26") (pinfunction "26_VCC_26") (pintype "bidirectional"))
      (node (ref "R38") (pin "2") (pinfunction "2_2") (pintype "passive"))
    )
    (net (code "81") (name "Net-(IC8-27_CP0)") (class "Default")
      (node (ref "C32") (pin "2") (pinfunction "2_2") (pintype "passive"))
      (node (ref "IC8") (pin "27") (pinfunction "27_CP0_27") (pintype "bidirectional"))
    )
    (net (code "82") (name "Net-(IC8-28_CPI)") (class "Default")
      (node (ref "C32") (pin "1") (pinfunction "1_1") (pintype "passive"))
      (node (ref "IC8") (pin "28") (pinfunction "28_CPI_28") (pintype "bidirectional"))
    )
    (net (code "83") (name "Net-(IC8-29_VCP)") (class "Default")
      (node (ref "C38") (pin "1") (pinfunction "1_1") (pintype "passive"))
      (node (ref "IC8") (pin "29") (pinfunction "29_VCP_29") (pintype "bidirectional"))
    )
    (net (code "84") (name "Net-(IC8-32_OA2)") (class "Default")
      (node (ref "IC8") (pin "32") (pinfunction "32_OA2_32") (pintype "bidirectional"))
      (node (ref "X8") (pin "1") (pinfunction "S_1") (pintype "passive"))
    )
    (net (code "85") (name "Net-(IC8-33_BRA)") (class "Default")
      (node (ref "IC8") (pin "33") (pinfunction "33_BRA_33") (pintype "bidirectional"))
      (node (ref "R35") (pin "2") (pinfunction "2_2") (pintype "passive"))
    )
    (net (code "86") (name "Net-(IC8-34_OA1)") (class "Default")
      (node (ref "IC8") (pin "34") (pinfunction "34_OA1_34") (pintype "bidirectional"))
      (node (ref "X8") (pin "2") (pinfunction "S_2") (pintype "passive"))
    )
    (net (code "87") (name "Net-(IC9A-I)") (class "Default")
      (node (ref "IC9") (pin "2") (pinfunction "I_2") (pintype "input"))
      (node (ref "U7") (pin "4") (pinfunction "QE_4") (pintype "output"))
    )
    (net (code "88") (name "Net-(IC9A-OE)") (class "Default")
      (node (ref "IC9") (pin "1") (pinfunction "OE_1") (pintype "input"))
      (node (ref "U7") (pin "5") (pinfunction "QF_5") (pintype "output"))
    )
    (net (code "89") (name "Net-(IC10A-I)") (class "Default")
      (node (ref "IC10") (pin "2") (pinfunction "I_2") (pintype "input"))
      (node (ref "U7") (pin "6") (pinfunction "QG_6") (pintype "output"))
    )
    (net (code "90") (name "Net-(IC10A-O)") (class "Default")
      (node (ref "IC10") (pin "4") (pinfunction "O_4") (pintype "output"))
      (node (ref "IC8") (pin "4") (pinfunction "4_SDI_CFG1_4") (pintype "bidirectional"))
    )
    (net (code "91") (name "Net-(IC10A-OE)") (class "Default")
      (node (ref "IC10") (pin "1") (pinfunction "OE_1") (pintype "input"))
      (node (ref "U7") (pin "7") (pinfunction "QH_7") (pintype "output"))
    )
    (net (code "92") (name "Net-(IC11A-I)") (class "Default")
      (node (ref "IC11") (pin "2") (pinfunction "I_2") (pintype "input"))
      (node (ref "U7") (pin "15") (pinfunction "QA_15") (pintype "output"))
    )
    (net (code "93") (name "Net-(IC18A-I)") (class "Default")
      (node (ref "IC18") (pin "2") (pinfunction "I_2") (pintype "input"))
      (node (ref "U1") (pin "15") (pinfunction "QA_15") (pintype "output"))
    )
    (net (code "94") (name "Net-(JP15-Pad1)") (class "Default")
      (node (ref "JP15") (pin "1") (pinfunction "1_1") (pintype "passive"))
      (node (ref "L3") (pin "2") (pinfunction "2_2") (pintype "passive"))
    )
    (net (code "95") (name "Net-(JP15-Pad2)") (class "Default")
      (node (ref "JP15") (pin "2") (pinfunction "2_2") (pintype "passive"))
      (node (ref "L1") (pin "2") (pinfunction "2_2") (pintype "passive"))
    )
    (net (code "96") (name "Net-(JP16-Pad1)") (class "Default")
      (node (ref "JP16") (pin "1") (pinfunction "1_1") (pintype "passive"))
      (node (ref "L5") (pin "2") (pinfunction "2_2") (pintype "passive"))
    )
    (net (code "97") (name "Net-(JP16-Pad2)") (class "Default")
      (node (ref "JP16") (pin "2") (pinfunction "2_2") (pintype "passive"))
      (node (ref "L4") (pin "2") (pinfunction "2_2") (pintype "passive"))
    )
    (net (code "98") (name "Net-(JP17-Pad1)") (class "Default")
      (node (ref "JP17") (pin "1") (pinfunction "1_1") (pintype "passive"))
      (node (ref "L7") (pin "2") (pinfunction "2_2") (pintype "passive"))
    )
    (net (code "99") (name "Net-(JP17-Pad2)") (class "Default")
      (node (ref "JP17") (pin "2") (pinfunction "2_2") (pintype "passive"))
      (node (ref "L6") (pin "2") (pinfunction "2_2") (pintype "passive"))
    )
    (net (code "100") (name "Net-(JP18-Pad1)") (class "Default")
      (node (ref "JP18") (pin "1") (pinfunction "1_1") (pintype "passive"))
      (node (ref "L9") (pin "2") (pinfunction "2_2") (pintype "passive"))
    )
    (net (code "101") (name "Net-(JP18-Pad2)") (class "Default")
      (node (ref "JP18") (pin "2") (pinfunction "2_2") (pintype "passive"))
      (node (ref "L8") (pin "2") (pinfunction "2_2") (pintype "passive"))
    )
    (net (code "102") (name "Net-(L1-Pad1)") (class "Default")
      (node (ref "L1") (pin "1") (pinfunction "1_1") (pintype "passive"))
      (node (ref "R51") (pin "1") (pinfunction "1_1") (pintype "passive"))
      (node (ref "R58") (pin "1") (pinfunction "1_1") (pintype "passive"))
    )
    (net (code "103") (name "Net-(L3-Pad1)") (class "Default")
      (node (ref "L3") (pin "1") (pinfunction "1_1") (pintype "passive"))
      (node (ref "R52") (pin "2") (pinfunction "2_2") (pintype "passive"))
      (node (ref "R56") (pin "1") (pinfunction "1_1") (pintype "passive"))
      (node (ref "R59") (pin "2") (pinfunction "2_2") (pintype "passive"))
    )
    (net (code "104") (name "Net-(L4-Pad1)") (class "Default")
      (node (ref "L4") (pin "1") (pinfunction "1_1") (pintype "passive"))
      (node (ref "R24") (pin "1") (pinfunction "1_1") (pintype "passive"))
      (node (ref "R27") (pin "1") (pinfunction "1_1") (pintype "passive"))
    )
    (net (code "105") (name "Net-(L5-Pad1)") (class "Default")
      (node (ref "L5") (pin "1") (pinfunction "1_1") (pintype "passive"))
      (node (ref "R22") (pin "1") (pinfunction "1_1") (pintype "passive"))
      (node (ref "R63") (pin "2") (pinfunction "2_2") (pintype "passive"))
      (node (ref "R64") (pin "2") (pinfunction "2_2") (pintype "passive"))
    )
    (net (code "106") (name "Net-(L6-Pad1)") (class "Default")
      (node (ref "L6") (pin "1") (pinfunction "1_1") (pintype "passive"))
      (node (ref "R71") (pin "1") (pinfunction "1_1") (pintype "passive"))
      (node (ref "R73") (pin "1") (pinfunction "1_1") (pintype "passive"))
    )
    (net (code "107") (name "Net-(L7-Pad1)") (class "Default")
      (node (ref "L7") (pin "1") (pinfunction "1_1") (pintype "passive"))
      (node (ref "R70") (pin "1") (pinfunction "1_1") (pintype "passive"))
      (node (ref "R74") (pin "2") (pinfunction "2_2") (pintype "passive"))
      (node (ref "R75") (pin "2") (pinfunction "2_2") (pintype "passive"))
    )
    (net (code "108") (name "Net-(L8-Pad1)") (class "Default")
      (node (ref "L8") (pin "1") (pinfunction "1_1") (pintype "passive"))
      (node (ref "R82") (pin "1") (pinfunction "1_1") (pintype "passive"))
      (node (ref "R84") (pin "1") (pinfunction "1_1") (pintype "passive"))
    )
    (net (code "109") (name "Net-(L9-Pad1)") (class "Default")
      (node (ref "L9") (pin "1") (pinfunction "1_1") (pintype "passive"))
      (node (ref "R81") (pin "1") (pinfunction "1_1") (pintype "passive"))
      (node (ref "R85") (pin "2") (pinfunction "2_2") (pintype "passive"))
      (node (ref "R86") (pin "2") (pinfunction "2_2") (pintype "passive"))
    )
    (net (code "110") (name "Net-(LED0-PadA)") (class "Default")
      (node (ref "LED0") (pin "A") (pinfunction "A_A") (pintype "passive"))
      (node (ref "R25") (pin "1") (pinfunction "1_1") (pintype "passive"))
    )
    (net (code "111") (name "Net-(LED1-PadA)") (class "Default")
      (node (ref "LED1") (pin "A") (pinfunction "A_A") (pintype "passive"))
      (node (ref "R14") (pin "1") (pinfunction "1_1") (pintype "passive"))
    )
    (net (code "112") (name "Net-(LED2-PadA)") (class "Default")
      (node (ref "LED2") (pin "A") (pinfunction "A_A") (pintype "passive"))
      (node (ref "R5") (pin "1") (pinfunction "1_1") (pintype "passive"))
    )
    (net (code "113") (name "Net-(LED3-PadA)") (class "Default")
      (node (ref "LED3") (pin "A") (pinfunction "A_A") (pintype "passive"))
      (node (ref "R15") (pin "1") (pinfunction "1_1") (pintype "passive"))
    )
    (net (code "114") (name "Net-(LED4-PadA)") (class "Default")
      (node (ref "LED4") (pin "A") (pinfunction "A_A") (pintype "passive"))
      (node (ref "R11") (pin "1") (pinfunction "1_1") (pintype "passive"))
    )
    (net (code "115") (name "Net-(LED5-PadA)") (class "Default")
      (node (ref "LED5") (pin "A") (pinfunction "A_A") (pintype "passive"))
      (node (ref "R20") (pin "1") (pinfunction "1_1") (pintype "passive"))
    )
    (net (code "116") (name "Net-(LED6-PadA)") (class "Default")
      (node (ref "LED6") (pin "A") (pinfunction "A_A") (pintype "passive"))
      (node (ref "R32") (pin "1") (pinfunction "1_1") (pintype "passive"))
    )
    (net (code "117") (name "Net-(LED8-PadC)") (class "Default")
      (node (ref "LED8") (pin "C") (pinfunction "C_C") (pintype "passive"))
      (node (ref "R45") (pin "2") (pinfunction "2_2") (pintype "passive"))
    )
    (net (code "118") (name "Net-(Q1-B)") (class "Default")
      (node (ref "Q1") (pin "1") (pinfunction "B_1") (pintype "passive"))
      (node (ref "R19") (pin "2") (pinfunction "2_2") (pintype "passive"))
      (node (ref "R77") (pin "1") (pinfunction "1_1") (pintype "passive"))
    )
    (net (code "119") (name "Net-(Q1-C)") (class "Default")
      (node (ref "LED2") (pin "C") (pinfunction "C_C") (pintype "passive"))
      (node (ref "Q1") (pin "3") (pinfunction "C_3") (pintype "passive"))
      (node (ref "X1") (pin "2") (pinfunction "S_2") (pintype "passive"))
    )
    (net (code "120") (name "Net-(Q2-G)") (class "Default")
      (node (ref "Q2") (pin "4") (pinfunction "G_4") (pintype "passive"))
      (node (ref "R48") (pin "2") (pinfunction "2_2") (pintype "passive"))
      (node (ref "R62") (pin "1") (pinfunction "1_1") (pintype "passive"))
    )
    (net (code "121") (name "Net-(Q3-G)") (class "Default")
      (node (ref "Q3") (pin "4") (pinfunction "G_4") (pintype "passive"))
      (node (ref "R47") (pin "2") (pinfunction "2_2") (pintype "passive"))
      (node (ref "R61") (pin "1") (pinfunction "1_1") (pintype "passive"))
    )
    (net (code "122") (name "Net-(Q4-B)") (class "Default")
      (node (ref "Q4") (pin "1") (pinfunction "B_1") (pintype "passive"))
      (node (ref "R21") (pin "2") (pinfunction "2_2") (pintype "passive"))
      (node (ref "R67") (pin "1") (pinfunction "1_1") (pintype "passive"))
    )
    (net (code "123") (name "Net-(Q4-C)") (class "Default")
      (node (ref "LED5") (pin "C") (pinfunction "C_C") (pintype "passive"))
      (node (ref "Q4") (pin "3") (pinfunction "C_3") (pintype "passive"))
      (node (ref "X4") (pin "2") (pinfunction "S_2") (pintype "passive"))
    )
    (net (code "124") (name "Net-(Q5-B)") (class "Default")
      (node (ref "Q5") (pin "1") (pinfunction "B_1") (pintype "passive"))
      (node (ref "R33") (pin "2") (pinfunction "2_2") (pintype "passive"))
      (node (ref "R66") (pin "1") (pinfunction "1_1") (pintype "passive"))
    )
    (net (code "125") (name "Net-(Q5-C)") (class "Default")
      (node (ref "LED6") (pin "C") (pinfunction "C_C") (pintype "passive"))
      (node (ref "Q5") (pin "3") (pinfunction "C_3") (pintype "passive"))
      (node (ref "X5") (pin "2") (pinfunction "S_2") (pintype "passive"))
    )
    (net (code "126") (name "Net-(Q6-B)") (class "Default")
      (node (ref "Q6") (pin "1") (pinfunction "B_1") (pintype "passive"))
      (node (ref "R34") (pin "2") (pinfunction "2_2") (pintype "passive"))
      (node (ref "R78") (pin "1") (pinfunction "1_1") (pintype "passive"))
    )
    (net (code "127") (name "Net-(Q6-C)") (class "Default")
      (node (ref "LED0") (pin "C") (pinfunction "C_C") (pintype "passive"))
      (node (ref "Q6") (pin "3") (pinfunction "C_3") (pintype "passive"))
      (node (ref "X9") (pin "2") (pinfunction "S_2") (pintype "passive"))
    )
    (net (code "128") (name "Net-(R26-Pad1)") (class "Default")
      (node (ref "R26") (pin "1") (pinfunction "1_1") (pintype "passive"))
      (node (ref "R27") (pin "2") (pinfunction "2_2") (pintype "passive"))
    )
    (net (code "129") (name "Net-(R29-Pad1)") (class "Default")
      (node (ref "R29") (pin "1") (pinfunction "1_1") (pintype "passive"))
      (node (ref "R30") (pin "2") (pinfunction "2_2") (pintype "passive"))
    )
    (net (code "130") (name "Net-(R50-Pad1)") (class "Default")
      (node (ref "R50") (pin "1") (pinfunction "1_1") (pintype "passive"))
      (node (ref "R51") (pin "2") (pinfunction "2_2") (pintype "passive"))
    )
    (net (code "131") (name "Net-(R59-Pad1)") (class "Default")
      (node (ref "R59") (pin "1") (pinfunction "1_1") (pintype "passive"))
      (node (ref "R60") (pin "2") (pinfunction "2_2") (pintype "passive"))
    )
    (net (code "132") (name "Net-(R64-Pad1)") (class "Default")
      (node (ref "R64") (pin "1") (pinfunction "1_1") (pintype "passive"))
      (node (ref "R65") (pin "2") (pinfunction "2_2") (pintype "passive"))
    )
    (net (code "133") (name "Net-(R72-Pad1)") (class "Default")
      (node (ref "R72") (pin "1") (pinfunction "1_1") (pintype "passive"))
      (node (ref "R73") (pin "2") (pinfunction "2_2") (pintype "passive"))
    )
    (net (code "134") (name "Net-(R75-Pad1)") (class "Default")
      (node (ref "R75") (pin "1") (pinfunction "1_1") (pintype "passive"))
      (node (ref "R76") (pin "2") (pinfunction "2_2") (pintype "passive"))
    )
    (net (code "135") (name "Net-(R83-Pad1)") (class "Default")
      (node (ref "R83") (pin "1") (pinfunction "1_1") (pintype "passive"))
      (node (ref "R84") (pin "2") (pinfunction "2_2") (pintype "passive"))
    )
    (net (code "136") (name "Net-(R86-Pad1)") (class "Default")
      (node (ref "R86") (pin "1") (pinfunction "1_1") (pintype "passive"))
      (node (ref "R87") (pin "2") (pinfunction "2_2") (pintype "passive"))
    )
    (net (code "137") (name "Net-(U3-ADDR)") (class "Default")
      (node (ref "R7") (pin "1") (pinfunction "1_1") (pintype "passive"))
      (node (ref "R8") (pin "2") (pinfunction "2_2") (pintype "passive"))
      (node (ref "U3") (pin "P$16") (pinfunction "ADDR_P$16") (pintype "bidirectional"))
    )
    (net (code "138") (name "Net-(U3-VIN+)") (class "Default")
      (node (ref "C49") (pin "2") (pinfunction "2_2") (pintype "passive"))
      (node (ref "R56") (pin "2") (pinfunction "2_2") (pintype "passive"))
      (node (ref "U3") (pin "P$2") (pinfunction "VIN+_P$2") (pintype "bidirectional"))
    )
    (net (code "139") (name "Net-(U3-VIN-)") (class "Default")
      (node (ref "C49") (pin "1") (pinfunction "1_1") (pintype "passive"))
      (node (ref "R58") (pin "2") (pinfunction "2_2") (pintype "passive"))
      (node (ref "U3") (pin "P$4") (pinfunction "VIN-_P$4") (pintype "bidirectional"))
    )
    (net (code "140") (name "Net-(U4-ADDR)") (class "Default")
      (node (ref "R13") (pin "1") (pinfunction "1_1") (pintype "passive"))
      (node (ref "R16") (pin "2") (pinfunction "2_2") (pintype "passive"))
      (node (ref "U4") (pin "P$16") (pinfunction "ADDR_P$16") (pintype "bidirectional"))
    )
    (net (code "141") (name "Net-(U4-VIN+)") (class "Default")
      (node (ref "C29") (pin "2") (pinfunction "2_2") (pintype "passive"))
      (node (ref "R22") (pin "2") (pinfunction "2_2") (pintype "passive"))
      (node (ref "U4") (pin "P$2") (pinfunction "VIN+_P$2") (pintype "bidirectional"))
    )
    (net (code "142") (name "Net-(U4-VIN-)") (class "Default")
      (node (ref "C29") (pin "1") (pinfunction "1_1") (pintype "passive"))
      (node (ref "R24") (pin "2") (pinfunction "2_2") (pintype "passive"))
      (node (ref "U4") (pin "P$4") (pinfunction "VIN-_P$4") (pintype "bidirectional"))
    )
    (net (code "143") (name "Net-(U5-ADDR)") (class "Default")
      (node (ref "R68") (pin "1") (pinfunction "1_1") (pintype "passive"))
      (node (ref "R69") (pin "2") (pinfunction "2_2") (pintype "passive"))
      (node (ref "U5") (pin "P$16") (pinfunction "ADDR_P$16") (pintype "bidirectional"))
    )
    (net (code "144") (name "Net-(U5-VIN+)") (class "Default")
      (node (ref "C50") (pin "2") (pinfunction "2_2") (pintype "passive"))
      (node (ref "R70") (pin "2") (pinfunction "2_2") (pintype "passive"))
      (node (ref "U5") (pin "P$2") (pinfunction "VIN+_P$2") (pintype "bidirectional"))
    )
    (net (code "145") (name "Net-(U5-VIN-)") (class "Default")
      (node (ref "C50") (pin "1") (pinfunction "1_1") (pintype "passive"))
      (node (ref "R71") (pin "2") (pinfunction "2_2") (pintype "passive"))
      (node (ref "U5") (pin "P$4") (pinfunction "VIN-_P$4") (pintype "bidirectional"))
    )
    (net (code "146") (name "Net-(U6-ADDR)") (class "Default")
      (node (ref "R79") (pin "1") (pinfunction "1_1") (pintype "passive"))
      (node (ref "R80") (pin "2") (pinfunction "2_2") (pintype "passive"))
      (node (ref "U6") (pin "P$16") (pinfunction "ADDR_P$16") (pintype "bidirectional"))
    )
    (net (code "147") (name "Net-(U6-VIN+)") (class "Default")
      (node (ref "C58") (pin "2") (pinfunction "2_2") (pintype "passive"))
      (node (ref "R81") (pin "2") (pinfunction "2_2") (pintype "passive"))
      (node (ref "U6") (pin "P$2") (pinfunction "VIN+_P$2") (pintype "bidirectional"))
    )
    (net (code "148") (name "Net-(U6-VIN-)") (class "Default")
      (node (ref "C58") (pin "1") (pinfunction "1_1") (pintype "passive"))
      (node (ref "R82") (pin "2") (pinfunction "2_2") (pintype "passive"))
      (node (ref "U6") (pin "P$4") (pinfunction "VIN-_P$4") (pintype "bidirectional"))
    )
    (net (code "149") (name "Net-(U10-BOOT)") (class "Default")
      (node (ref "C55") (pin "1") (pinfunction "1_1") (pintype "passive"))
      (node (ref "U10") (pin "2") (pinfunction "BOOT_2") (pintype "input"))
    )
    (net (code "150") (name "Net-(U10-COMP)") (class "Default")
      (node (ref "C56") (pin "1") (pinfunction "1_1") (pintype "passive"))
      (node (ref "U10") (pin "8") (pinfunction "COMP_8") (pintype "bidirectional"))
    )
    (net (code "151") (name "Net-(U10-FB)") (class "Default")
      (node (ref "R42") (pin "2") (pinfunction "2_2") (pintype "passive"))
      (node (ref "R43") (pin "1") (pinfunction "1_1") (pintype "passive"))
      (node (ref "U10") (pin "7") (pinfunction "FB_7") (pintype "input"))
    )
    (net (code "152") (name "Net-(U10-SS)") (class "Default")
      (node (ref "C54") (pin "1") (pinfunction "1_1") (pintype "passive"))
      (node (ref "U10") (pin "10") (pinfunction "SS_10") (pintype "bidirectional"))
    )
    (net (code "153") (name "Net-(U10-SW)") (class "Default")
      (node (ref "C55") (pin "2") (pinfunction "2_2") (pintype "passive"))
      (node (ref "D4") (pin "C") (pinfunction "C_C") (pintype "passive"))
      (node (ref "L2") (pin "P$2") (pinfunction "P$2_P$2") (pintype "passive"))
      (node (ref "U10") (pin "5") (pinfunction "SW_5") (pintype "power_in"))
    )
    (net (code "154") (name "Net-(X3B-1)") (class "Default")
      (node (ref "C59") (pin "1") (pinfunction "1_1") (pintype "passive"))
      (node (ref "D1") (pin "A") (pinfunction "A_A") (pintype "passive"))
      (node (ref "LED3") (pin "C") (pinfunction "C_C") (pintype "passive"))
      (node (ref "Q3") (pin "5") (pinfunction "D_5") (pintype "passive"))
      (node (ref "Q3") (pin "6") (pinfunction "D_6") (pintype "passive"))
      (node (ref "Q3") (pin "7") (pinfunction "D_7") (pintype "passive"))
      (node (ref "Q3") (pin "8") (pinfunction "D_8") (pintype "passive"))
      (node (ref "Q3") (pin "TH") (pinfunction "D_TH") (pintype "passive"))
      (node (ref "R55") (pin "1") (pinfunction "1_1") (pintype "passive"))
      (node (ref "X3") (pin "2") (pinfunction "1_2") (pintype "passive"))
    )
    (net (code "155") (name "Net-(X7B-S)") (class "Default")
      (node (ref "R17") (pin "1") (pinfunction "1_1") (pintype "passive"))
      (node (ref "R39") (pin "1") (pinfunction "1_1") (pintype "passive"))
      (node (ref "X7") (pin "2") (pinfunction "S_2") (pintype "passive"))
    )
    (net (code "156") (name "Net-(X11B-S)") (class "Default")
      (node (ref "R18") (pin "1") (pinfunction "1_1") (pintype "passive"))
      (node (ref "R40") (pin "1") (pinfunction "1_1") (pintype "passive"))
      (node (ref "X11") (pin "2") (pinfunction "S_2") (pintype "passive"))
    )
    (net (code "157") (name "Net-(X21B-1)") (class "Default")
      (node (ref "C57") (pin "1") (pinfunction "1_1") (pintype "passive"))
      (node (ref "D3") (pin "A") (pinfunction "A_A") (pintype "passive"))
      (node (ref "LED1") (pin "C") (pinfunction "C_C") (pintype "passive"))
      (node (ref "Q2") (pin "5") (pinfunction "D_5") (pintype "passive"))
      (node (ref "Q2") (pin "6") (pinfunction "D_6") (pintype "passive"))
      (node (ref "Q2") (pin "7") (pinfunction "D_7") (pintype "passive"))
      (node (ref "Q2") (pin "8") (pinfunction "D_8") (pintype "passive"))
      (node (ref "Q2") (pin "TH") (pinfunction "D_TH") (pintype "passive"))
      (node (ref "R57") (pin "1") (pinfunction "1_1") (pintype "passive"))
      (node (ref "X21") (pin "2") (pinfunction "1_2") (pintype "passive"))
    )
    (net (code "158") (name "SER_2") (class "Default")
      (node (ref "U1") (pin "9") (pinfunction "QH_2_9") (pintype "output"))
      (node (ref "U2") (pin "14") (pinfunction "SER_14") (pintype "input"))
    )
    (net (code "159") (name "SER_3") (class "Default")
      (node (ref "U2") (pin "9") (pinfunction "QH_2_9") (pintype "output"))
      (node (ref "U7") (pin "14") (pinfunction "SER_14") (pintype "input"))
    )
    (net (code "160") (name "SPI1_CS0") (class "Default")
      (node (ref "P9") (pin "27") (pinfunction "27_27") (pintype "passive"))
      (node (ref "U1") (pin "12") (pinfunction "RCLK_12") (pintype "input"))
      (node (ref "U2") (pin "12") (pinfunction "RCLK_12") (pintype "input"))
      (node (ref "U7") (pin "12") (pinfunction "RCLK_12") (pintype "input"))
    )
    (net (code "161") (name "SPI1_MOSI") (class "Default")
      (node (ref "P9") (pin "30") (pinfunction "30_30") (pintype "passive"))
      (node (ref "U1") (pin "14") (pinfunction "SER_14") (pintype "input"))
    )
    (net (code "162") (name "SPI1_SCLK") (class "Default")
      (node (ref "P9") (pin "31") (pinfunction "31_31") (pintype "passive"))
      (node (ref "U1") (pin "11") (pinfunction "SRCLK_11") (pintype "input"))
      (node (ref "U2") (pin "11") (pinfunction "SRCLK_11") (pintype "input"))
      (node (ref "U7") (pin "11") (pinfunction "SRCLK_11") (pintype "input"))
    )
    (net (code "163") (name "STEP_A") (class "Default")
      (node (ref "IC1") (pin "6") (pinfunction "6_STEP_6") (pintype "bidirectional"))
      (node (ref "P9") (pin "26") (pinfunction "26_26") (pintype "passive"))
    )
    (net (code "164") (name "STEP_B") (class "Default")
      (node (ref "IC2") (pin "6") (pinfunction "6_STEP_6") (pintype "bidirectional"))
      (node (ref "P8") (pin "7") (pinfunction "7_7") (pintype "passive"))
    )
    (net (code "165") (name "STEP_C") (class "Default")
      (node (ref "IC8") (pin "6") (pinfunction "6_STEP_6") (pintype "bidirectional"))
      (node (ref "P9") (pin "15") (pinfunction "15_15") (pintype "passive"))
    )
    (net (code "166") (name "THERMO_2") (class "Default")
      (node (ref "P9") (pin "38") (pinfunction "38_38") (pintype "passive"))
    )
    (net (code "167") (name "THERM_EXT3") (class "Default")
      (node (ref "C46") (pin "1") (pinfunction "1_1") (pintype "passive"))
      (node (ref "P9") (pin "39") (pinfunction "39_39") (pintype "passive"))
      (node (ref "R40") (pin "2") (pinfunction "2_2") (pintype "passive"))
    )
    (net (code "168") (name "THERM_EXT4") (class "Default")
      (node (ref "C45") (pin "1") (pinfunction "1_1") (pintype "passive"))
      (node (ref "P9") (pin "40") (pinfunction "40_40") (pintype "passive"))
      (node (ref "R39") (pin "2") (pinfunction "2_2") (pintype "passive"))
    )
    (net (code "169") (name "TRISTATE_STEPPERS") (class "Default")
      (node (ref "IC11") (pin "1") (pinfunction "OE_1") (pintype "input"))
      (node (ref "IC18") (pin "1") (pinfunction "OE_1") (pintype "input"))
      (node (ref "IC7") (pin "1") (pinfunction "OE_1") (pintype "input"))
    )
    (net (code "170") (name "VDD_5V") (class "Default")
      (node (ref "C17") (pin "1") (pinfunction "1_1") (pintype "passive"))
      (node (ref "P9") (pin "5") (pinfunction "5_5") (pintype "passive"))
      (node (ref "P9") (pin "6") (pinfunction "6_6") (pintype "passive"))
      (node (ref "U11") (pin "1") (pinfunction "A0_1") (pintype "input"))
      (node (ref "U11") (pin "2") (pinfunction "A1_2") (pintype "input"))
      (node (ref "U11") (pin "28") (pinfunction "VDD_28") (pintype "power_in"))
      (node (ref "U11") (pin "3") (pinfunction "A2_3") (pintype "input"))
      (node (ref "U11") (pin "4") (pinfunction "A3_4") (pintype "input"))
      (node (ref "U11") (pin "5") (pinfunction "A4_5") (pintype "input"))
    )
    (net (code "171") (name "VDD_12V") (class "Default")
      (node (ref "12V") (pin "TP") (pinfunction "TP_TP") (pintype "input"))
      (node (ref "C53") (pin "1") (pinfunction "1_1") (pintype "passive"))
      (node (ref "C81") (pin "1") (pinfunction "1_1") (pintype "passive"))
      (node (ref "L2") (pin "P$1") (pinfunction "P$1_P$1") (pintype "passive"))
      (node (ref "R11") (pin "2") (pinfunction "2_2") (pintype "passive"))
      (node (ref "R20") (pin "2") (pinfunction "2_2") (pintype "passive"))
      (node (ref "R25") (pin "2") (pinfunction "2_2") (pintype "passive"))
      (node (ref "R32") (pin "2") (pinfunction "2_2") (pintype "passive"))
      (node (ref "R42") (pin "1") (pinfunction "1_1") (pintype "passive"))
      (node (ref "R5") (pin "2") (pinfunction "2_2") (pintype "passive"))
      (node (ref "X1") (pin "1") (pinfunction "S_1") (pintype "passive"))
      (node (ref "X4") (pin "1") (pinfunction "S_1") (pintype "passive"))
      (node (ref "X5") (pin "1") (pinfunction "S_1") (pintype "passive"))
      (node (ref "X9") (pin "1") (pinfunction "S_1") (pintype "passive"))
    )
    (net (code "172") (name "VDD_ADC") (class "Default")
      (node (ref "P9") (pin "32") (pinfunction "32_32") (pintype "passive"))
      (node (ref "R17") (pin "2") (pinfunction "2_2") (pintype "passive"))
      (node (ref "R18") (pin "2") (pinfunction "2_2") (pintype "passive"))
    )
    (net (code "173") (name "VDD_IN") (class "Default")
      (node (ref "12..24V") (pin "TP") (pinfunction "TP_TP") (pintype "input"))
      (node (ref "C14") (pin "2") (pinfunction "2_2") (pintype "passive"))
      (node (ref "C16") (pin "2") (pinfunction "2_2") (pintype "passive"))
      (node (ref "C20") (pin "2") (pinfunction "2_2") (pintype "passive"))
      (node (ref "C22") (pin "2") (pinfunction "2_2") (pintype "passive"))
      (node (ref "C24") (pin "1") (pinfunction "1_1") (pintype "passive"))
      (node (ref "C25") (pin "1") (pinfunction "1_1") (pintype "passive"))
      (node (ref "C27") (pin "1") (pinfunction "1_1") (pintype "passive"))
      (node (ref "C28") (pin "+") (pinfunction "+_+") (pintype "passive"))
      (node (ref "C36") (pin "2") (pinfunction "2_2") (pintype "passive"))
      (node (ref "C38") (pin "2") (pinfunction "2_2") (pintype "passive"))
      (node (ref "C4") (pin "1") (pinfunction "1_1") (pintype "passive"))
      (node (ref "C43") (pin "1") (pinfunction "1_1") (pintype "passive"))
      (node (ref "C44") (pin "1") (pinfunction "1_1") (pintype "passive"))
      (node (ref "C47") (pin "1") (pinfunction "1_1") (pintype "passive"))
      (node (ref "C48") (pin "+") (pinfunction "+_+") (pintype "passive"))
      (node (ref "C52") (pin "1") (pinfunction "1_1") (pintype "passive"))
      (node (ref "C6") (pin "1") (pinfunction "1_1") (pintype "passive"))
      (node (ref "C7") (pin "1") (pinfunction "1_1") (pintype "passive"))
      (node (ref "C8") (pin "+") (pinfunction "+_+") (pintype "passive"))
      (node (ref "D1") (pin "C") (pinfunction "C_C") (pintype "passive"))
      (node (ref "D3") (pin "C") (pinfunction "C_C") (pintype "passive"))
      (node (ref "D5") (pin "C") (pinfunction "C_C") (pintype "passive"))
      (node (ref "F1") (pin "P$3") (pinfunction "2_P$3") (pintype "passive"))
      (node (ref "F1") (pin "P$4") (pinfunction "2_P$4") (pintype "passive"))
      (node (ref "IC1") (pin "16") (pinfunction "16_VS_16") (pintype "bidirectional"))
      (node (ref "IC1") (pin "30") (pinfunction "30_VSA_30") (pintype "bidirectional"))
      (node (ref "IC1") (pin "31") (pinfunction "31_VS_31") (pintype "bidirectional"))
      (node (ref "IC2") (pin "16") (pinfunction "16_VS_16") (pintype "bidirectional"))
      (node (ref "IC2") (pin "30") (pinfunction "30_VSA_30") (pintype "bidirectional"))
      (node (ref "IC2") (pin "31") (pinfunction "31_VS_31") (pintype "bidirectional"))
      (node (ref "IC8") (pin "16") (pinfunction "16_VS_16") (pintype "bidirectional"))
      (node (ref "IC8") (pin "30") (pinfunction "30_VSA_30") (pintype "bidirectional"))
      (node (ref "IC8") (pin "31") (pinfunction "31_VS_31") (pintype "bidirectional"))
      (node (ref "R14") (pin "2") (pinfunction "2_2") (pintype "passive"))
      (node (ref "R15") (pin "2") (pinfunction "2_2") (pintype "passive"))
      (node (ref "R45") (pin "1") (pinfunction "1_1") (pintype "passive"))
      (node (ref "R55") (pin "2") (pinfunction "2_2") (pintype "passive"))
      (node (ref "R57") (pin "2") (pinfunction "2_2") (pintype "passive"))
      (node (ref "U10") (pin "4") (pinfunction "VIN_4") (pintype "power_in"))
      (node (ref "X21") (pin "1") (pinfunction "1_1") (pintype "passive"))
      (node (ref "X3") (pin "1") (pinfunction "1_1") (pintype "passive"))
    )
    (net (code "174") (name "VIN") (class "Default")
      (node (ref "F1") (pin "P$1") (pinfunction "1_P$1") (pintype "passive"))
      (node (ref "F1") (pin "P$2") (pinfunction "1_P$2") (pintype "passive"))
      (node (ref "LED8") (pin "A") (pinfunction "A_A") (pintype "passive"))
      (node (ref "X2") (pin "3") (pinfunction "1_3") (pintype "passive"))
      (node (ref "X2") (pin "4") (pinfunction "1_4") (pintype "passive"))
    )
    (net (code "175") (name "unconnected-(IC1-2_CSN_CFG3-Pad2)") (class "Default")
      (node (ref "IC1") (pin "2") (pinfunction "2_CSN_CFG3_2") (pintype "bidirectional"))
    )
    (net (code "176") (name "unconnected-(IC1-9_NC-Pad9)") (class "Default")
      (node (ref "IC1") (pin "9") (pinfunction "9_NC_9") (pintype "bidirectional"))
    )
    (net (code "177") (name "unconnected-(IC1-11_NC-Pad11)") (class "Default")
      (node (ref "IC1") (pin "11") (pinfunction "11_NC_11") (pintype "bidirectional"))
    )
    (net (code "178") (name "unconnected-(IC1-17_DC0-Pad17)") (class "Default")
      (node (ref "IC1") (pin "17") (pinfunction "17_DC0_17") (pintype "bidirectional"))
    )
    (net (code "179") (name "unconnected-(IC1-21_DIAG1-Pad21)") (class "Default")
      (node (ref "IC1") (pin "21") (pinfunction "21_DIAG1_21") (pintype "bidirectional"))
    )
    (net (code "180") (name "unconnected-(IC2-2_CSN_CFG3-Pad2)") (class "Default")
      (node (ref "IC2") (pin "2") (pinfunction "2_CSN_CFG3_2") (pintype "bidirectional"))
    )
    (net (code "181") (name "unconnected-(IC2-9_NC-Pad9)") (class "Default")
      (node (ref "IC2") (pin "9") (pinfunction "9_NC_9") (pintype "bidirectional"))
    )
    (net (code "182") (name "unconnected-(IC2-11_NC-Pad11)") (class "Default")
      (node (ref "IC2") (pin "11") (pinfunction "11_NC_11") (pintype "bidirectional"))
    )
    (net (code "183") (name "unconnected-(IC2-17_DC0-Pad17)") (class "Default")
      (node (ref "IC2") (pin "17") (pinfunction "17_DC0_17") (pintype "bidirectional"))
    )
    (net (code "184") (name "unconnected-(IC2-21_DIAG1-Pad21)") (class "Default")
      (node (ref "IC2") (pin "21") (pinfunction "21_DIAG1_21") (pintype "bidirectional"))
    )
    (net (code "185") (name "unconnected-(IC8-2_CSN_CFG3-Pad2)") (class "Default")
      (node (ref "IC8") (pin "2") (pinfunction "2_CSN_CFG3_2") (pintype "bidirectional"))
    )
    (net (code "186") (name "unconnected-(IC8-9_NC-Pad9)") (class "Default")
      (node (ref "IC8") (pin "9") (pinfunction "9_NC_9") (pintype "bidirectional"))
    )
    (net (code "187") (name "unconnected-(IC8-11_NC-Pad11)") (class "Default")
      (node (ref "IC8") (pin "11") (pinfunction "11_NC_11") (pintype "bidirectional"))
    )
    (net (code "188") (name "unconnected-(IC8-17_DC0-Pad17)") (class "Default")
      (node (ref "IC8") (pin "17") (pinfunction "17_DC0_17") (pintype "bidirectional"))
    )
    (net (code "189") (name "unconnected-(IC8-21_DIAG1-Pad21)") (class "Default")
      (node (ref "IC8") (pin "21") (pinfunction "21_DIAG1_21") (pintype "bidirectional"))
    )
    (net (code "190") (name "unconnected-(P8-Pad3)") (class "Default")
      (node (ref "P8") (pin "3") (pinfunction "3_3") (pintype "passive"))
    )
    (net (code "191") (name "unconnected-(P8-Pad4)") (class "Default")
      (node (ref "P8") (pin "4") (pinfunction "4_4") (pintype "passive"))
    )
    (net (code "192") (name "unconnected-(P8-Pad5)") (class "Default")
      (node (ref "P8") (pin "5") (pinfunction "5_5") (pintype "passive"))
    )
    (net (code "193") (name "unconnected-(P8-Pad6)") (class "Default")
      (node (ref "P8") (pin "6") (pinfunction "6_6") (pintype "passive"))
    )
    (net (code "194") (name "unconnected-(P8-Pad8)") (class "Default")
      (node (ref "P8") (pin "8") (pinfunction "8_8") (pintype "passive"))
    )
    (net (code "195") (name "unconnected-(P8-Pad9)") (class "Default")
      (node (ref "P8") (pin "9") (pinfunction "9_9") (pintype "passive"))
    )
    (net (code "196") (name "unconnected-(P8-Pad10)") (class "Default")
      (node (ref "P8") (pin "10") (pinfunction "10_10") (pintype "passive"))
    )
    (net (code "197") (name "unconnected-(P8-Pad11)") (class "Default")
      (node (ref "P8") (pin "11") (pinfunction "11_11") (pintype "passive"))
    )
    (net (code "198") (name "unconnected-(P8-Pad12)") (class "Default")
      (node (ref "P8") (pin "12") (pinfunction "12_12") (pintype "passive"))
    )
    (net (code "199") (name "unconnected-(P8-Pad13)") (class "Default")
      (node (ref "P8") (pin "13") (pinfunction "13_13") (pintype "passive"))
    )
    (net (code "200") (name "unconnected-(P8-Pad14)") (class "Default")
      (node (ref "P8") (pin "14") (pinfunction "14_14") (pintype "passive"))
    )
    (net (code "201") (name "unconnected-(P8-Pad15)") (class "Default")
      (node (ref "P8") (pin "15") (pinfunction "15_15") (pintype "passive"))
    )
    (net (code "202") (name "unconnected-(P8-Pad16)") (class "Default")
      (node (ref "P8") (pin "16") (pinfunction "16_16") (pintype "passive"))
    )
    (net (code "203") (name "unconnected-(P8-Pad17)") (class "Default")
      (node (ref "P8") (pin "17") (pinfunction "17_17") (pintype "passive"))
    )
    (net (code "204") (name "unconnected-(P8-Pad18)") (class "Default")
      (node (ref "P8") (pin "18") (pinfunction "18_18") (pintype "passive"))
    )
    (net (code "205") (name "unconnected-(P8-Pad19)") (class "Default")
      (node (ref "P8") (pin "19") (pinfunction "19_19") (pintype "passive"))
    )
    (net (code "206") (name "unconnected-(P8-Pad20)") (class "Default")
      (node (ref "P8") (pin "20") (pinfunction "20_20") (pintype "passive"))
    )
    (net (code "207") (name "unconnected-(P8-Pad21)") (class "Default")
      (node (ref "P8") (pin "21") (pinfunction "21_21") (pintype "passive"))
    )
    (net (code "208") (name "unconnected-(P8-Pad22)") (class "Default")
      (node (ref "P8") (pin "22") (pinfunction "22_22") (pintype "passive"))
    )
    (net (code "209") (name "unconnected-(P8-Pad23)") (class "Default")
      (node (ref "P8") (pin "23") (pinfunction "23_23") (pintype "passive"))
    )
    (net (code "210") (name "unconnected-(P8-Pad24)") (class "Default")
      (node (ref "P8") (pin "24") (pinfunction "24_24") (pintype "passive"))
    )
    (net (code "211") (name "unconnected-(P8-Pad25)") (class "Default")
      (node (ref "P8") (pin "25") (pinfunction "25_25") (pintype "passive"))
    )
    (net (code "212") (name "unconnected-(P8-Pad26)") (class "Default")
      (node (ref "P8") (pin "26") (pinfunction "26_26") (pintype "passive"))
    )
    (net (code "213") (name "unconnected-(P8-Pad27)") (class "Default")
      (node (ref "P8") (pin "27") (pinfunction "27_27") (pintype "passive"))
    )
    (net (code "214") (name "unconnected-(P8-Pad28)") (class "Default")
      (node (ref "P8") (pin "28") (pinfunction "28_28") (pintype "passive"))
    )
    (net (code "215") (name "unconnected-(P8-Pad29)") (class "Default")
      (node (ref "P8") (pin "29") (pinfunction "29_29") (pintype "passive"))
    )
    (net (code "216") (name "unconnected-(P8-Pad30)") (class "Default")
      (node (ref "P8") (pin "30") (pinfunction "30_30") (pintype "passive"))
    )
    (net (code "217") (name "unconnected-(P8-Pad31)") (class "Default")
      (node (ref "P8") (pin "31") (pinfunction "31_31") (pintype "passive"))
    )
    (net (code "218") (name "unconnected-(P8-Pad32)") (class "Default")
      (node (ref "P8") (pin "32") (pinfunction "32_32") (pintype "passive"))
    )
    (net (code "219") (name "unconnected-(P8-Pad33)") (class "Default")
      (node (ref "P8") (pin "33") (pinfunction "33_33") (pintype "passive"))
    )
    (net (code "220") (name "unconnected-(P8-Pad34)") (class "Default")
      (node (ref "P8") (pin "34") (pinfunction "34_34") (pintype "passive"))
    )
    (net (code "221") (name "unconnected-(P8-Pad35)") (class "Default")
      (node (ref "P8") (pin "35") (pinfunction "35_35") (pintype "passive"))
    )
    (net (code "222") (name "unconnected-(P8-Pad36)") (class "Default")
      (node (ref "P8") (pin "36") (pinfunction "36_36") (pintype "passive"))
    )
    (net (code "223") (name "unconnected-(P8-Pad37)") (class "Default")
      (node (ref "P8") (pin "37") (pinfunction "37_37") (pintype "passive"))
    )
    (net (code "224") (name "unconnected-(P8-Pad38)") (class "Default")
      (node (ref "P8") (pin "38") (pinfunction "38_38") (pintype "passive"))
    )
    (net (code "225") (name "unconnected-(P8-Pad39)") (class "Default")
      (node (ref "P8") (pin "39") (pinfunction "39_39") (pintype "passive"))
    )
    (net (code "226") (name "unconnected-(P8-Pad40)") (class "Default")
      (node (ref "P8") (pin "40") (pinfunction "40_40") (pintype "passive"))
    )
    (net (code "227") (name "unconnected-(P8-Pad41)") (class "Default")
      (node (ref "P8") (pin "41") (pinfunction "41_41") (pintype "passive"))
    )
    (net (code "228") (name "unconnected-(P8-Pad42)") (class "Default")
      (node (ref "P8") (pin "42") (pinfunction "42_42") (pintype "passive"))
    )
    (net (code "229") (name "unconnected-(P8-Pad43)") (class "Default")
      (node (ref "P8") (pin "43") (pinfunction "43_43") (pintype "passive"))
    )
    (net (code "230") (name "unconnected-(P8-Pad44)") (class "Default")
      (node (ref "P8") (pin "44") (pinfunction "44_44") (pintype "passive"))
    )
    (net (code "231") (name "unconnected-(P8-Pad45)") (class "Default")
      (node (ref "P8") (pin "45") (pinfunction "45_45") (pintype "passive"))
    )
    (net (code "232") (name "unconnected-(P8-Pad46)") (class "Default")
      (node (ref "P8") (pin "46") (pinfunction "46_46") (pintype "passive"))
    )
    (net (code "233") (name "unconnected-(P9-Pad7)") (class "Default")
      (node (ref "P9") (pin "7") (pinfunction "7_7") (pintype "passive"))
    )
    (net (code "234") (name "unconnected-(P9-Pad8)") (class "Default")
      (node (ref "P9") (pin "8") (pinfunction "8_8") (pintype "passive"))
    )
    (net (code "235") (name "unconnected-(P9-Pad9)") (class "Default")
      (node (ref "P9") (pin "9") (pinfunction "9_9") (pintype "passive"))
    )
    (net (code "236") (name "unconnected-(P9-Pad10)") (class "Default")
      (node (ref "P9") (pin "10") (pinfunction "10_10") (pintype "passive"))
    )
    (net (code "237") (name "unconnected-(P9-Pad11)") (class "Default")
      (node (ref "P9") (pin "11") (pinfunction "11_11") (pintype "passive"))
    )
    (net (code "238") (name "unconnected-(P9-Pad12)") (class "Default")
      (node (ref "P9") (pin "12") (pinfunction "12_12") (pintype "passive"))
    )
    (net (code "239") (name "unconnected-(P9-Pad13)") (class "Default")
      (node (ref "P9") (pin "13") (pinfunction "13_13") (pintype "passive"))
    )
    (net (code "240") (name "unconnected-(P9-Pad14)") (class "Default")
      (node (ref "P9") (pin "14") (pinfunction "14_14") (pintype "passive"))
    )
    (net (code "241") (name "unconnected-(P9-Pad16)") (class "Default")
      (node (ref "P9") (pin "16") (pinfunction "16_16") (pintype "passive"))
    )
    (net (code "242") (name "unconnected-(P9-Pad18)") (class "Default")
      (node (ref "P9") (pin "18") (pinfunction "18_18") (pintype "passive"))
    )
    (net (code "243") (name "unconnected-(P9-Pad22)") (class "Default")
      (node (ref "P9") (pin "22") (pinfunction "22_22") (pintype "passive"))
    )
    (net (code "244") (name "unconnected-(P9-Pad23)") (class "Default")
      (node (ref "P9") (pin "23") (pinfunction "23_23") (pintype "passive"))
    )
    (net (code "245") (name "unconnected-(P9-Pad24)") (class "Default")
      (node (ref "P9") (pin "24") (pinfunction "24_24") (pintype "passive"))
    )
    (net (code "246") (name "unconnected-(P9-Pad25)") (class "Default")
      (node (ref "P9") (pin "25") (pinfunction "25_25") (pintype "passive"))
    )
    (net (code "247") (name "unconnected-(P9-Pad28)") (class "Default")
      (node (ref "P9") (pin "28") (pinfunction "28_28") (pintype "passive"))
    )
    (net (code "248") (name "unconnected-(P9-Pad33)") (class "Default")
      (node (ref "P9") (pin "33") (pinfunction "33_33") (pintype "passive"))
    )
    (net (code "249") (name "unconnected-(P9-Pad34)") (class "Default")
      (node (ref "P9") (pin "34") (pinfunction "34_34") (pintype "passive"))
    )
    (net (code "250") (name "unconnected-(P9-Pad35)") (class "Default")
      (node (ref "P9") (pin "35") (pinfunction "35_35") (pintype "passive"))
    )
    (net (code "251") (name "unconnected-(P9-Pad36)") (class "Default")
      (node (ref "P9") (pin "36") (pinfunction "36_36") (pintype "passive"))
    )
    (net (code "252") (name "unconnected-(P9-Pad42)") (class "Default")
      (node (ref "P9") (pin "42") (pinfunction "42_42") (pintype "passive"))
    )
    (net (code "253") (name "unconnected-(U3-ALERT1-PadP$11)") (class "Default")
      (node (ref "U3") (pin "P$11") (pinfunction "ALERT1_P$11") (pintype "bidirectional"))
    )
    (net (code "254") (name "unconnected-(U3-ALERT2-PadP$12)") (class "Default")
      (node (ref "U3") (pin "P$12") (pinfunction "ALERT2_P$12") (pintype "bidirectional"))
    )
    (net (code "255") (name "unconnected-(U3-ALERT3-PadP$14)") (class "Default")
      (node (ref "U3") (pin "P$14") (pinfunction "ALERT3_P$14") (pintype "bidirectional"))
    )
    (net (code "256") (name "unconnected-(U3-ALERT4-PadP$15)") (class "Default")
      (node (ref "U3") (pin "P$15") (pinfunction "ALERT4_P$15") (pintype "bidirectional"))
    )
    (net (code "257") (name "unconnected-(U4-ALERT1-PadP$11)") (class "Default")
      (node (ref "U4") (pin "P$11") (pinfunction "ALERT1_P$11") (pintype "bidirectional"))
    )
    (net (code "258") (name "unconnected-(U4-ALERT2-PadP$12)") (class "Default")
      (node (ref "U4") (pin "P$12") (pinfunction "ALERT2_P$12") (pintype "bidirectional"))
    )
    (net (code "259") (name "unconnected-(U4-ALERT3-PadP$14)") (class "Default")
      (node (ref "U4") (pin "P$14") (pinfunction "ALERT3_P$14") (pintype "bidirectional"))
    )
    (net (code "260") (name "unconnected-(U4-ALERT4-PadP$15)") (class "Default")
      (node (ref "U4") (pin "P$15") (pinfunction "ALERT4_P$15") (pintype "bidirectional"))
    )
    (net (code "261") (name "unconnected-(U5-ALERT1-PadP$11)") (class "Default")
      (node (ref "U5") (pin "P$11") (pinfunction "ALERT1_P$11") (pintype "bidirectional"))
    )
    (net (code "262") (name "unconnected-(U5-ALERT2-PadP$12)") (class "Default")
      (node (ref "U5") (pin "P$12") (pinfunction "ALERT2_P$12") (pintype "bidirectional"))
    )
    (net (code "263") (name "unconnected-(U5-ALERT3-PadP$14)") (class "Default")
      (node (ref "U5") (pin "P$14") (pinfunction "ALERT3_P$14") (pintype "bidirectional"))
    )
    (net (code "264") (name "unconnected-(U5-ALERT4-PadP$15)") (class "Default")
      (node (ref "U5") (pin "P$15") (pinfunction "ALERT4_P$15") (pintype "bidirectional"))
    )
    (net (code "265") (name "unconnected-(U6-ALERT1-PadP$11)") (class "Default")
      (node (ref "U6") (pin "P$11") (pinfunction "ALERT1_P$11") (pintype "bidirectional"))
    )
    (net (code "266") (name "unconnected-(U6-ALERT2-PadP$12)") (class "Default")
      (node (ref "U6") (pin "P$12") (pinfunction "ALERT2_P$12") (pintype "bidirectional"))
    )
    (net (code "267") (name "unconnected-(U6-ALERT3-PadP$14)") (class "Default")
      (node (ref "U6") (pin "P$14") (pinfunction "ALERT3_P$14") (pintype "bidirectional"))
    )
    (net (code "268") (name "unconnected-(U6-ALERT4-PadP$15)") (class "Default")
      (node (ref "U6") (pin "P$15") (pinfunction "ALERT4_P$15") (pintype "bidirectional"))
    )
    (net (code "269") (name "unconnected-(U7-QH_2-Pad9)") (class "Default")
      (node (ref "U7") (pin "9") (pinfunction "QH_2_9") (pintype "output"))
    )
    (net (code "270") (name "unconnected-(U10-EN-Pad9)") (class "Default")
      (node (ref "U10") (pin "9") (pinfunction "EN_9") (pintype "input"))
    )
    (net (code "271") (name "unconnected-(U11-EXTCLK-Pad25)") (class "Default")
      (node (ref "U11") (pin "25") (pinfunction "EXTCLK_25") (pintype "input"))
    )
    (net (code "272") (name "unconnected-(U11-LED0-Pad6)") (class "Default")
      (node (ref "U11") (pin "6") (pinfunction "LED0_6") (pintype "output"))
    )
    (net (code "273") (name "unconnected-(U11-LED1-Pad7)") (class "Default")
      (node (ref "U11") (pin "7") (pinfunction "LED1_7") (pintype "output"))
    )
    (net (code "274") (name "unconnected-(U11-LED2-Pad8)") (class "Default")
      (node (ref "U11") (pin "8") (pinfunction "LED2_8") (pintype "output"))
    )
    (net (code "275") (name "unconnected-(U11-LED4-Pad10)") (class "Default")
      (node (ref "U11") (pin "10") (pinfunction "LED4_10") (pintype "output"))
    )
    (net (code "276") (name "unconnected-(U11-LED6-Pad12)") (class "Default")
      (node (ref "U11") (pin "12") (pinfunction "LED6_12") (pintype "output"))
    )
    (net (code "277") (name "unconnected-(U11-LED14-Pad21)") (class "Default")
      (node (ref "U11") (pin "21") (pinfunction "LED14_21") (pintype "output"))
    )
    (net (code "278") (name "unconnected-(U11-LED15-Pad22)") (class "Default")
      (node (ref "U11") (pin "22") (pinfunction "LED15_22") (pintype "output"))
    )
    (net (code "279") (name "unconnected-(U18-~{WC}-Pad7)") (class "Default")
      (node (ref "U18") (pin "7") (pinfunction "~{WC}_7") (pintype "no_connect"))
    )
  )
)
